# MK-312BT_V1_2.net
KiCad netlist of a schematic drawn in EAGLE
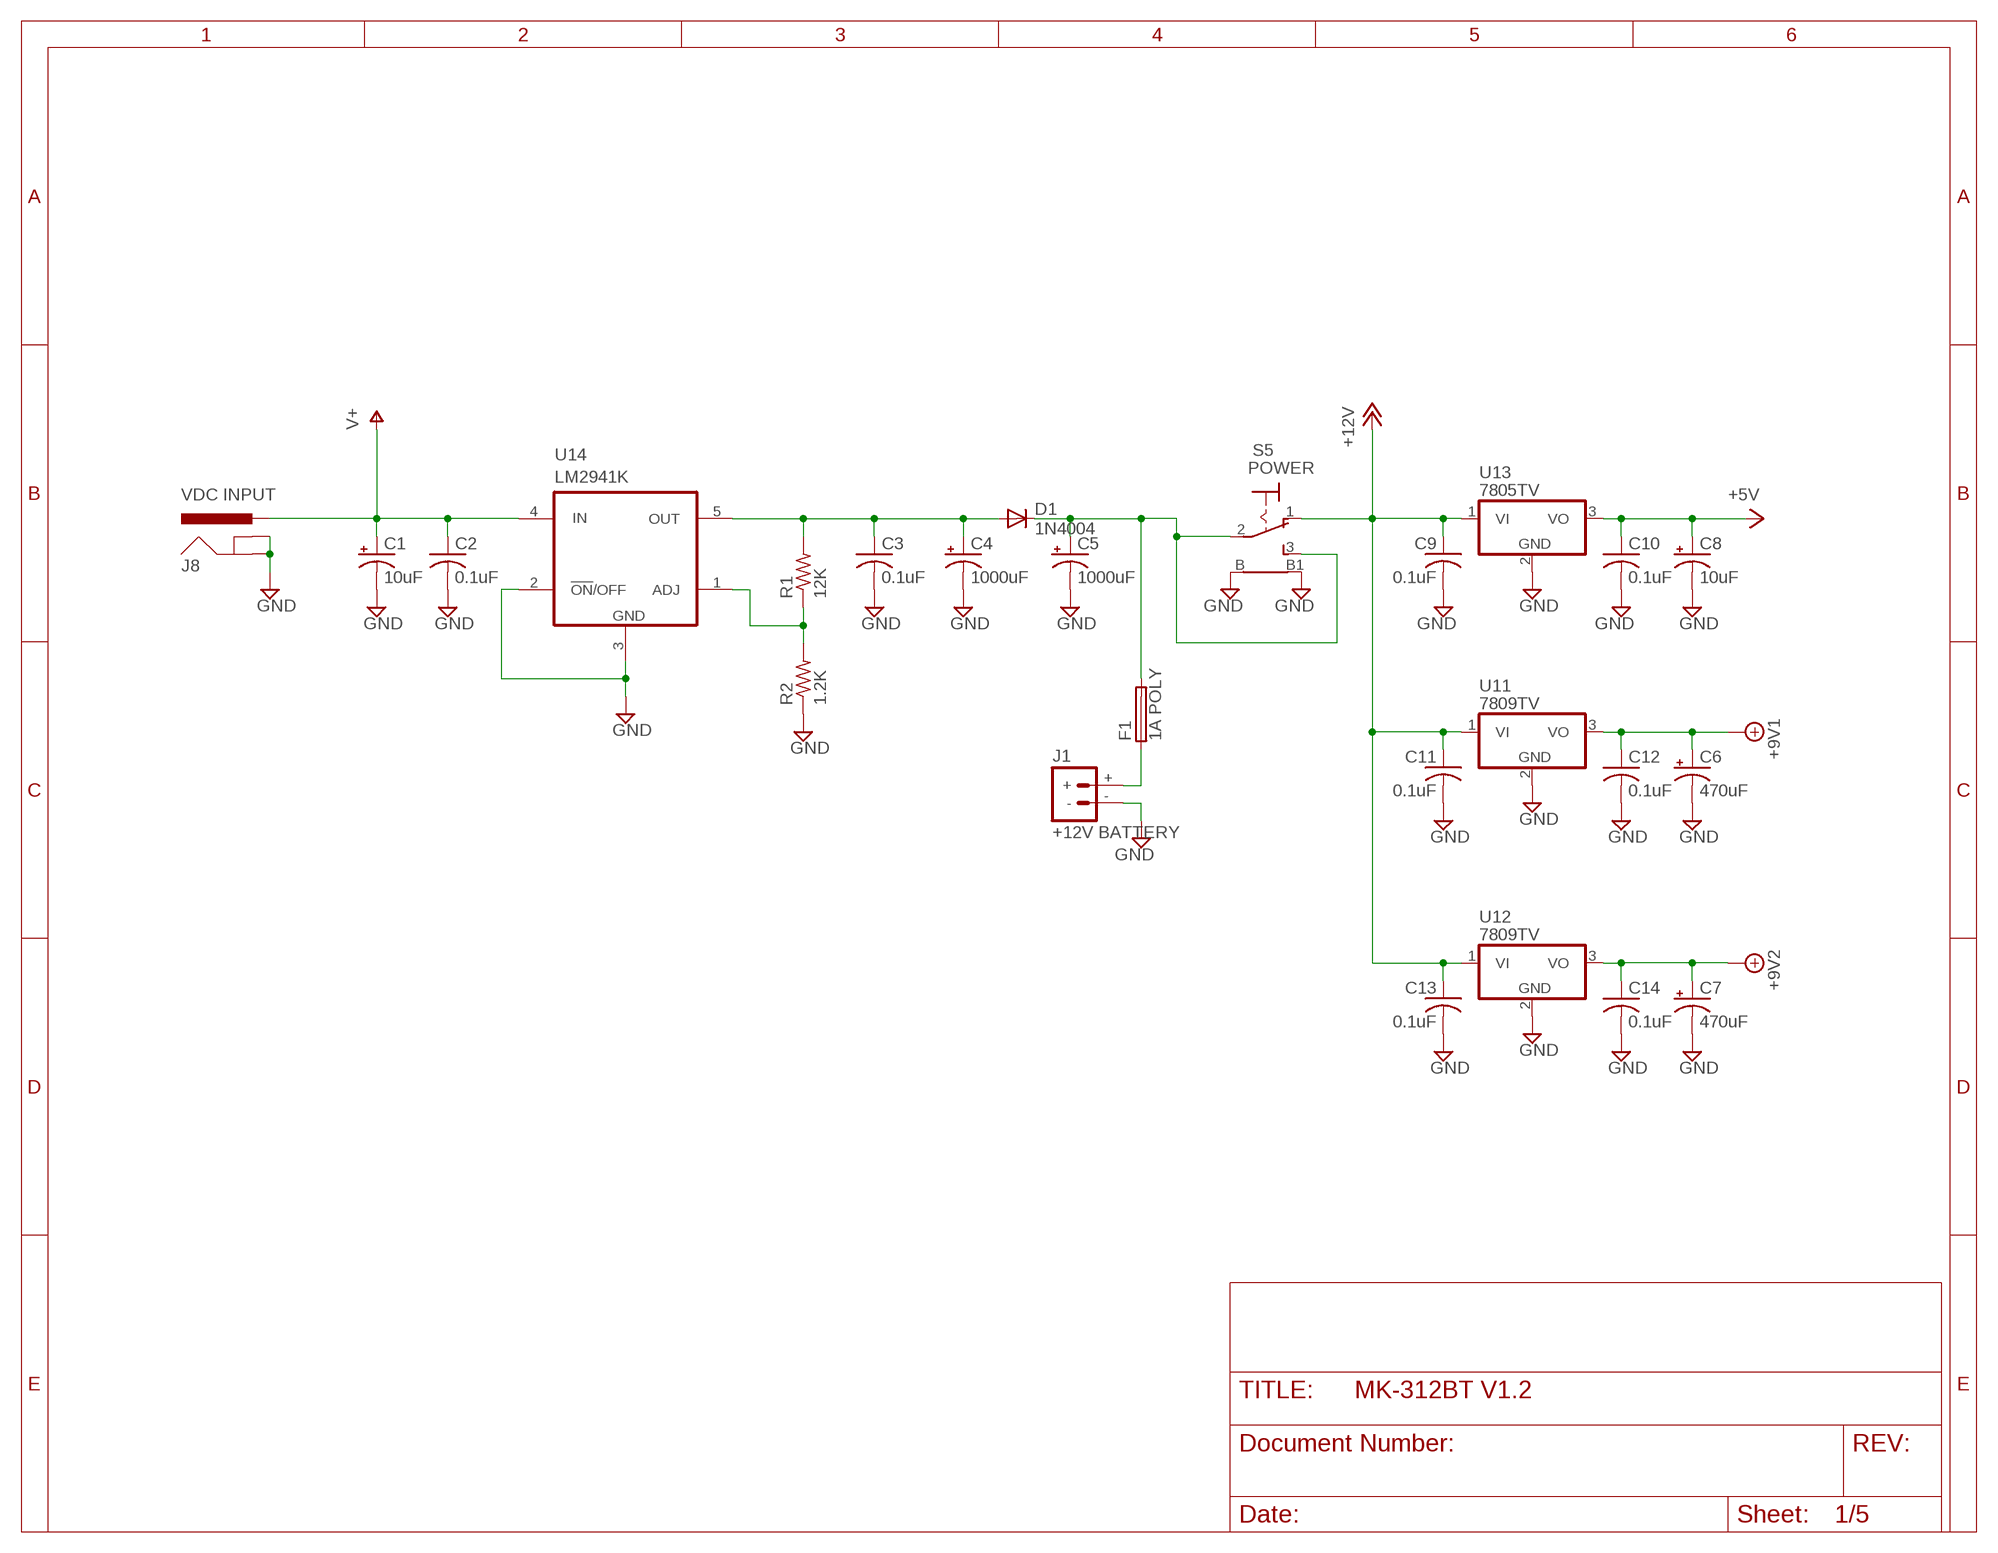
[diagram p0: schematic, sheet 1]
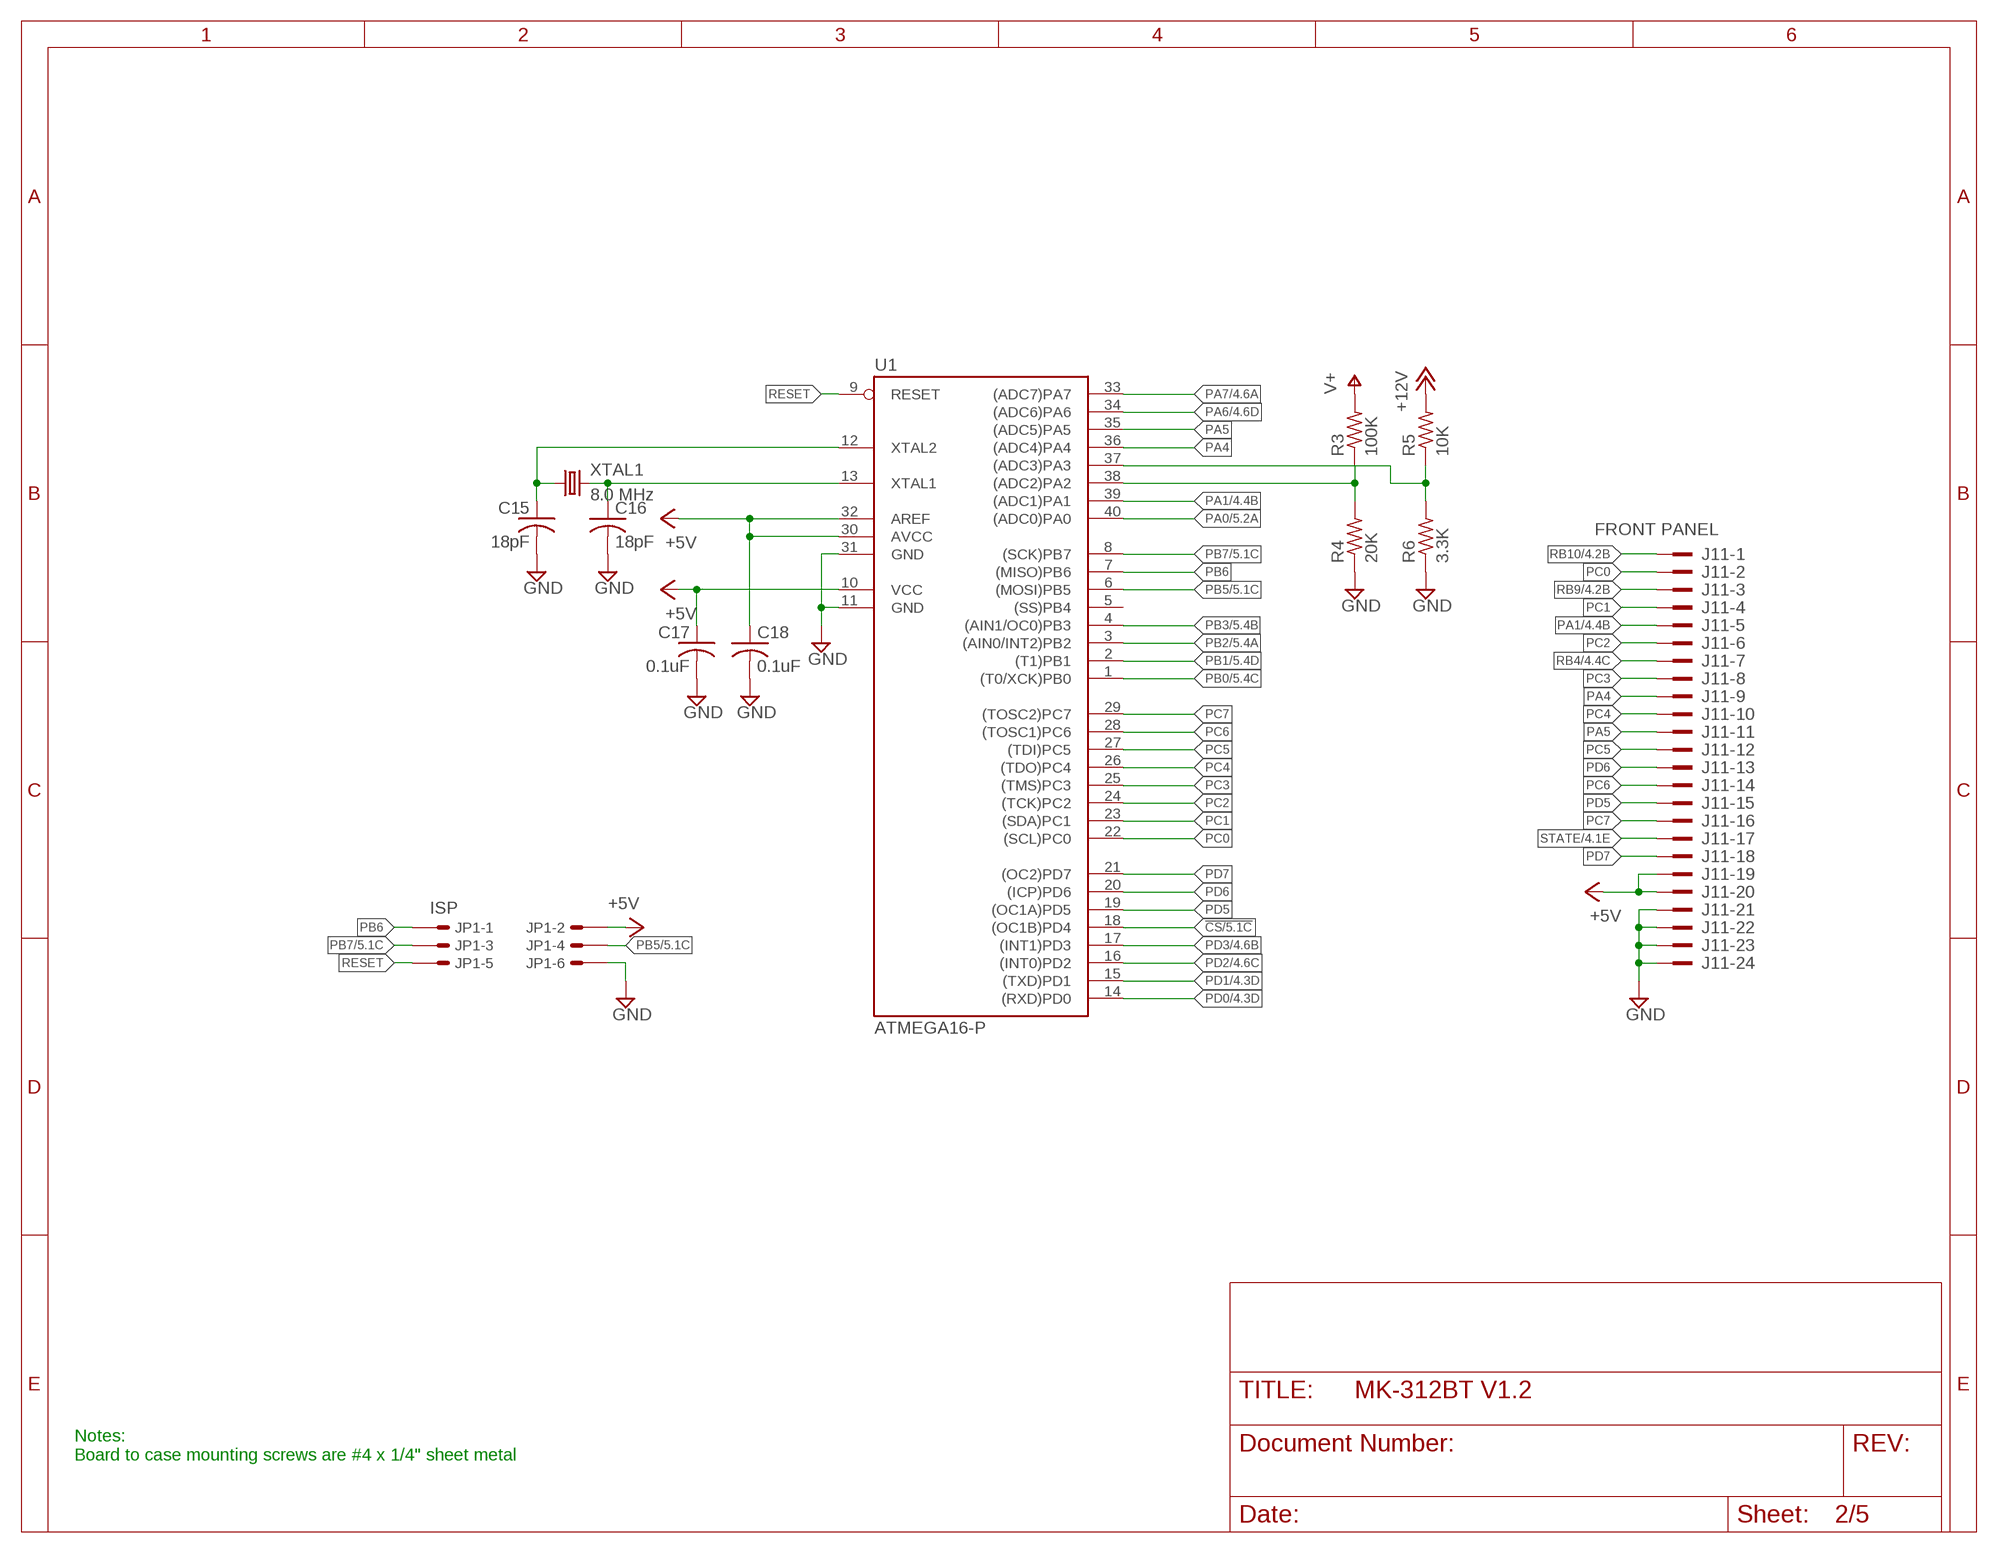
[diagram p1: schematic, sheet 2]
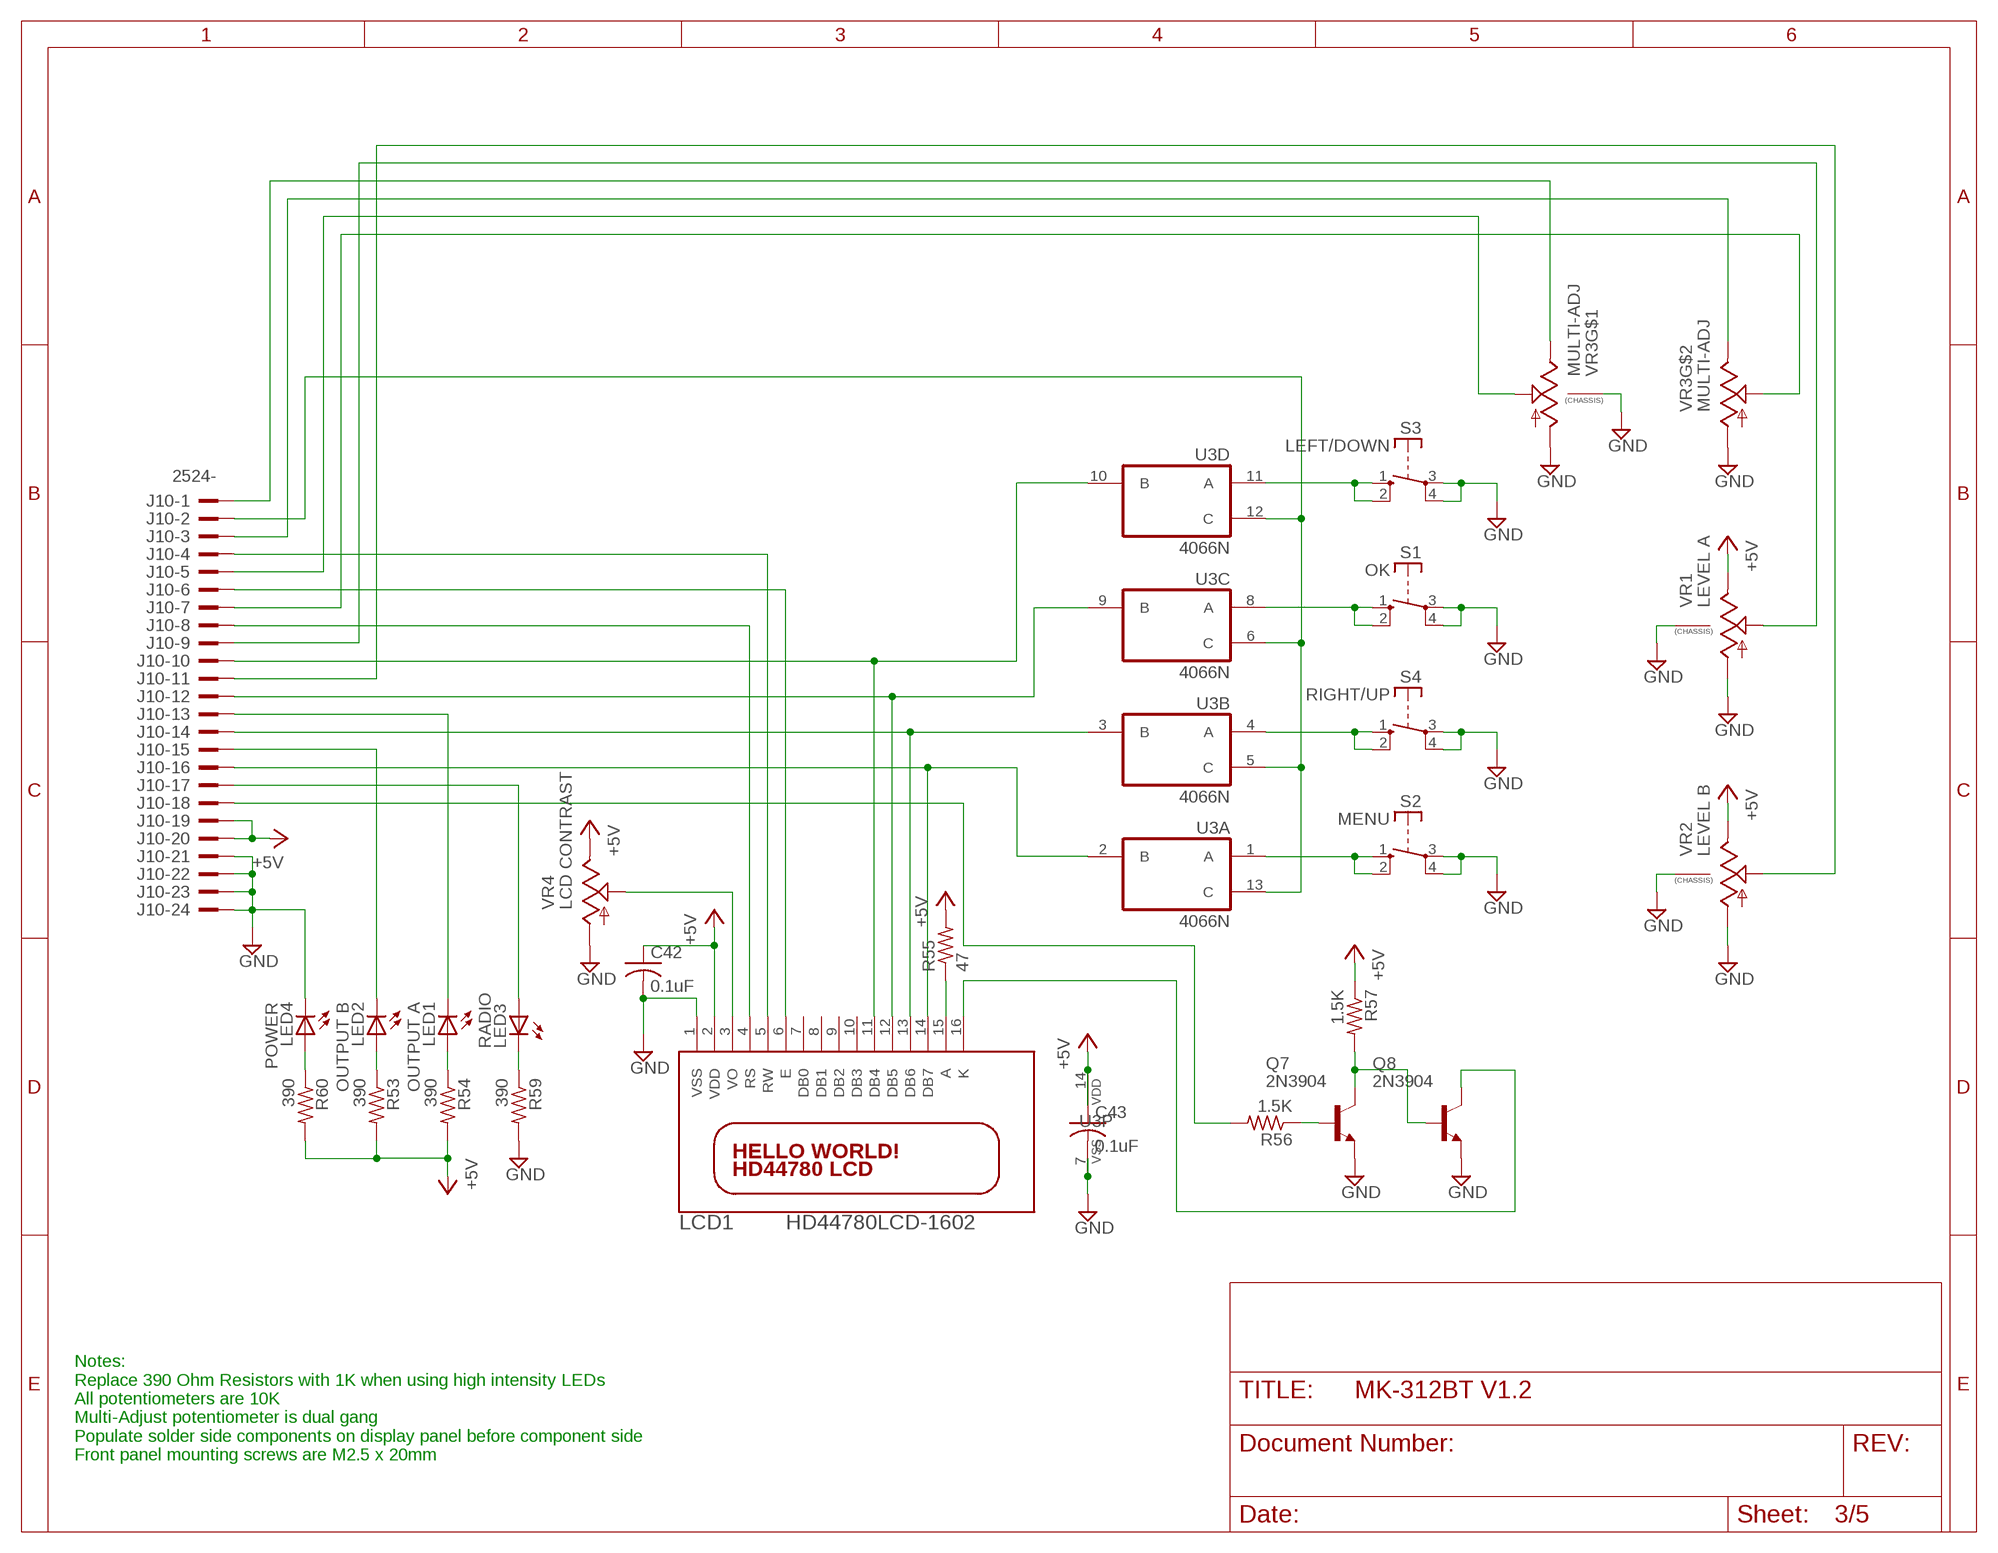
[diagram p2: schematic, sheet 3]
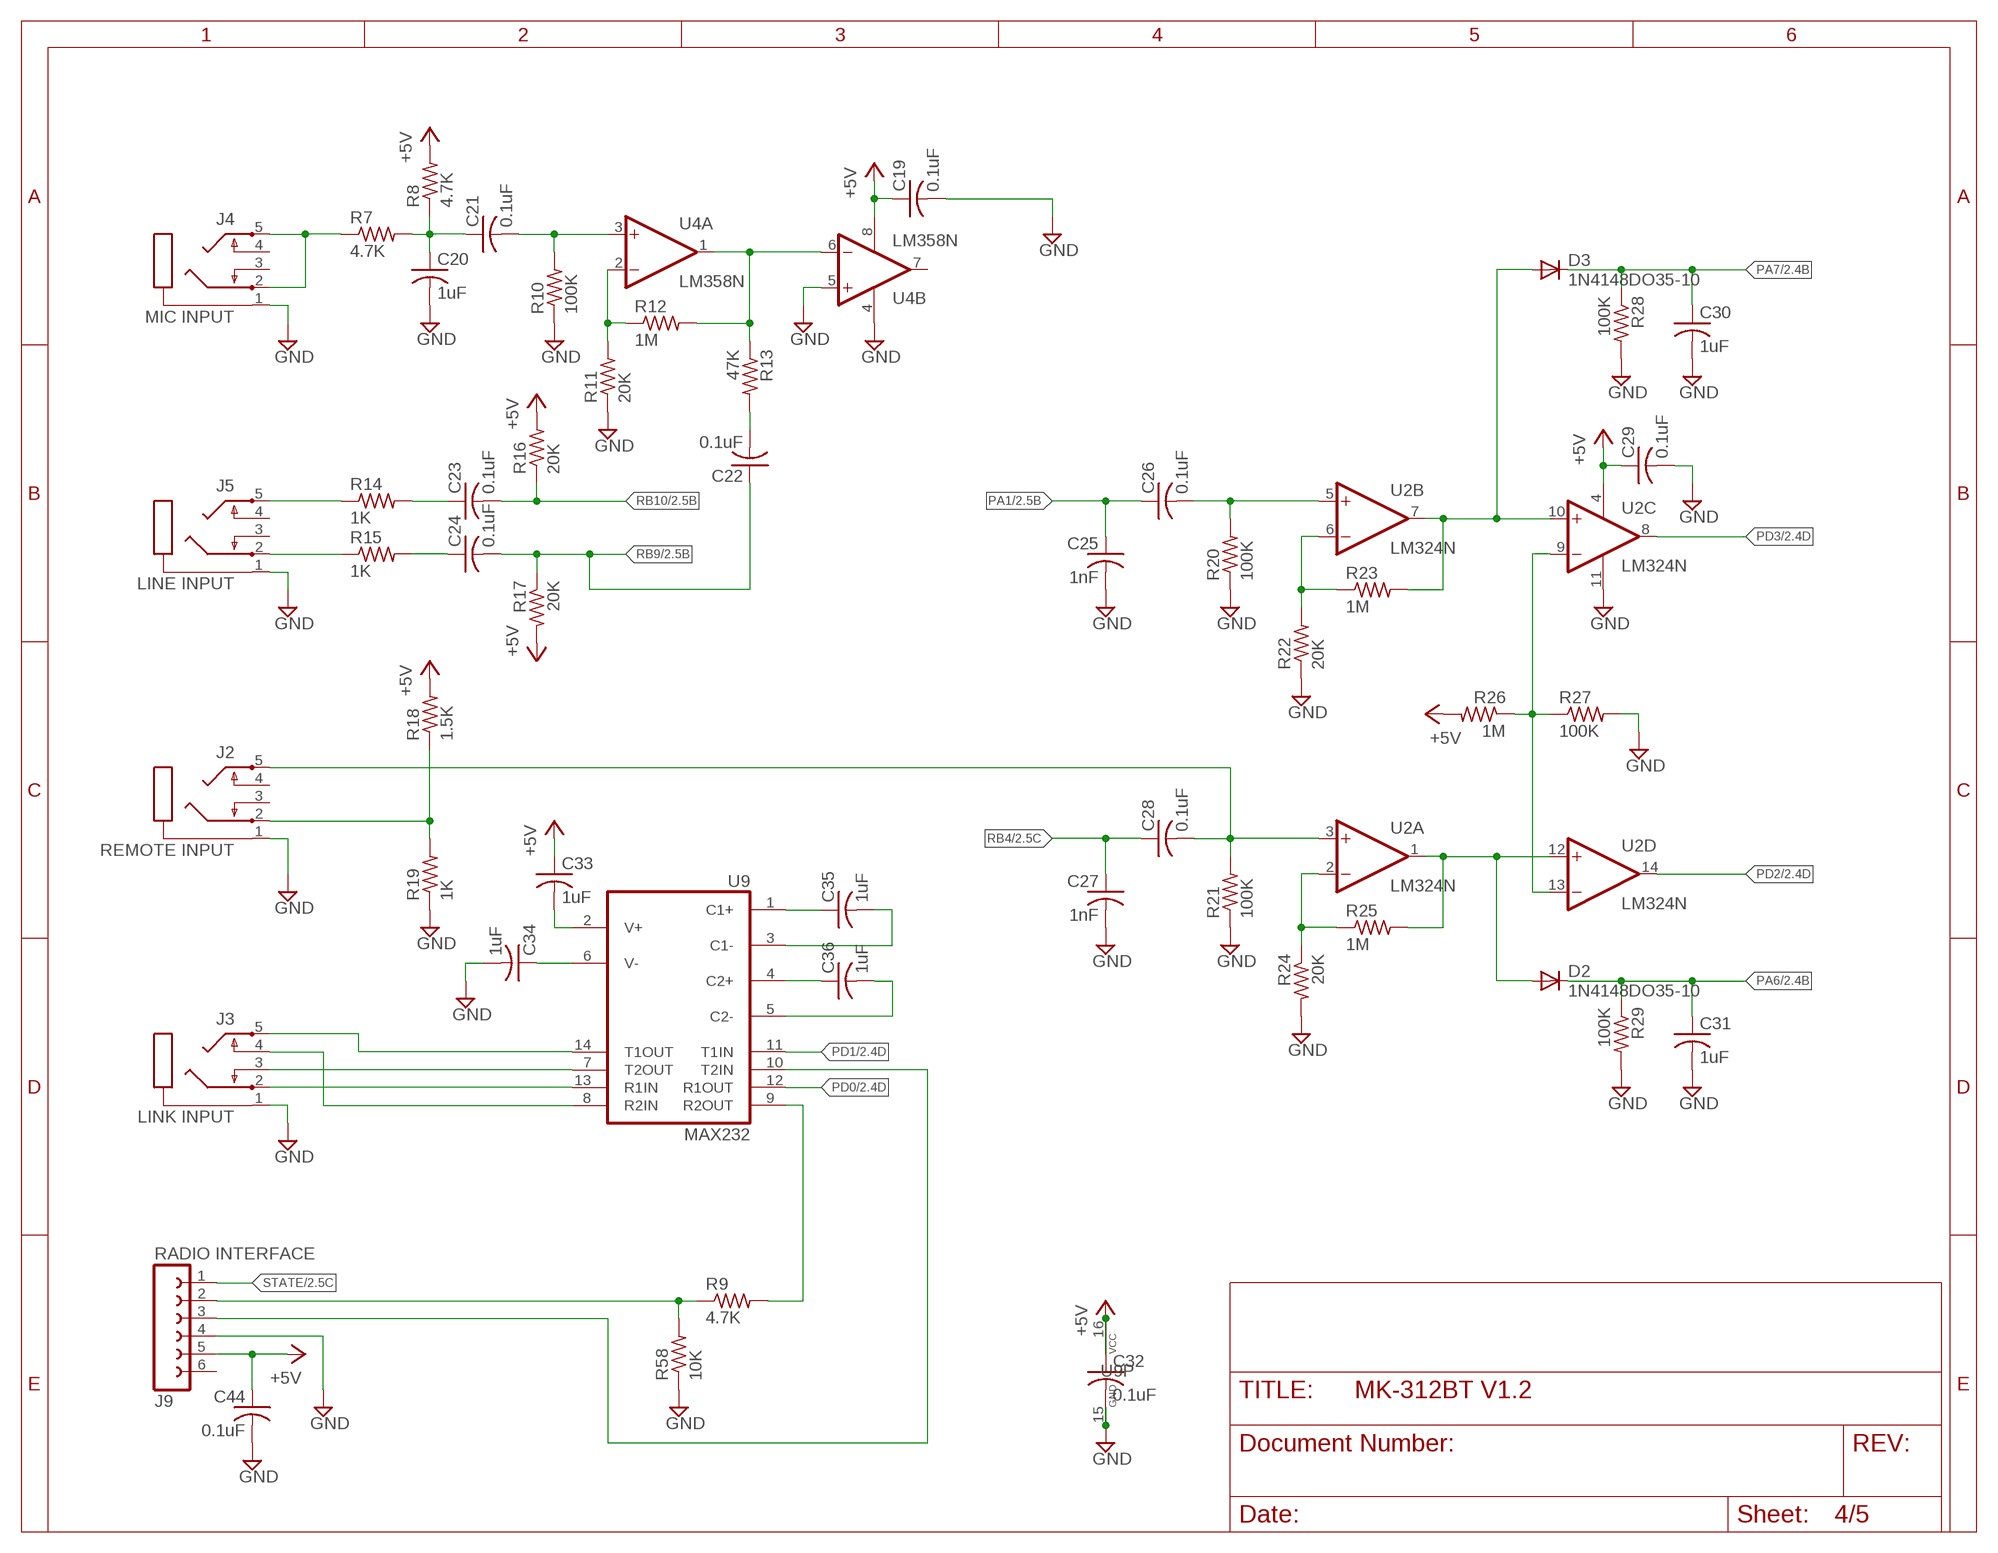
[diagram p3: schematic, sheet 4]
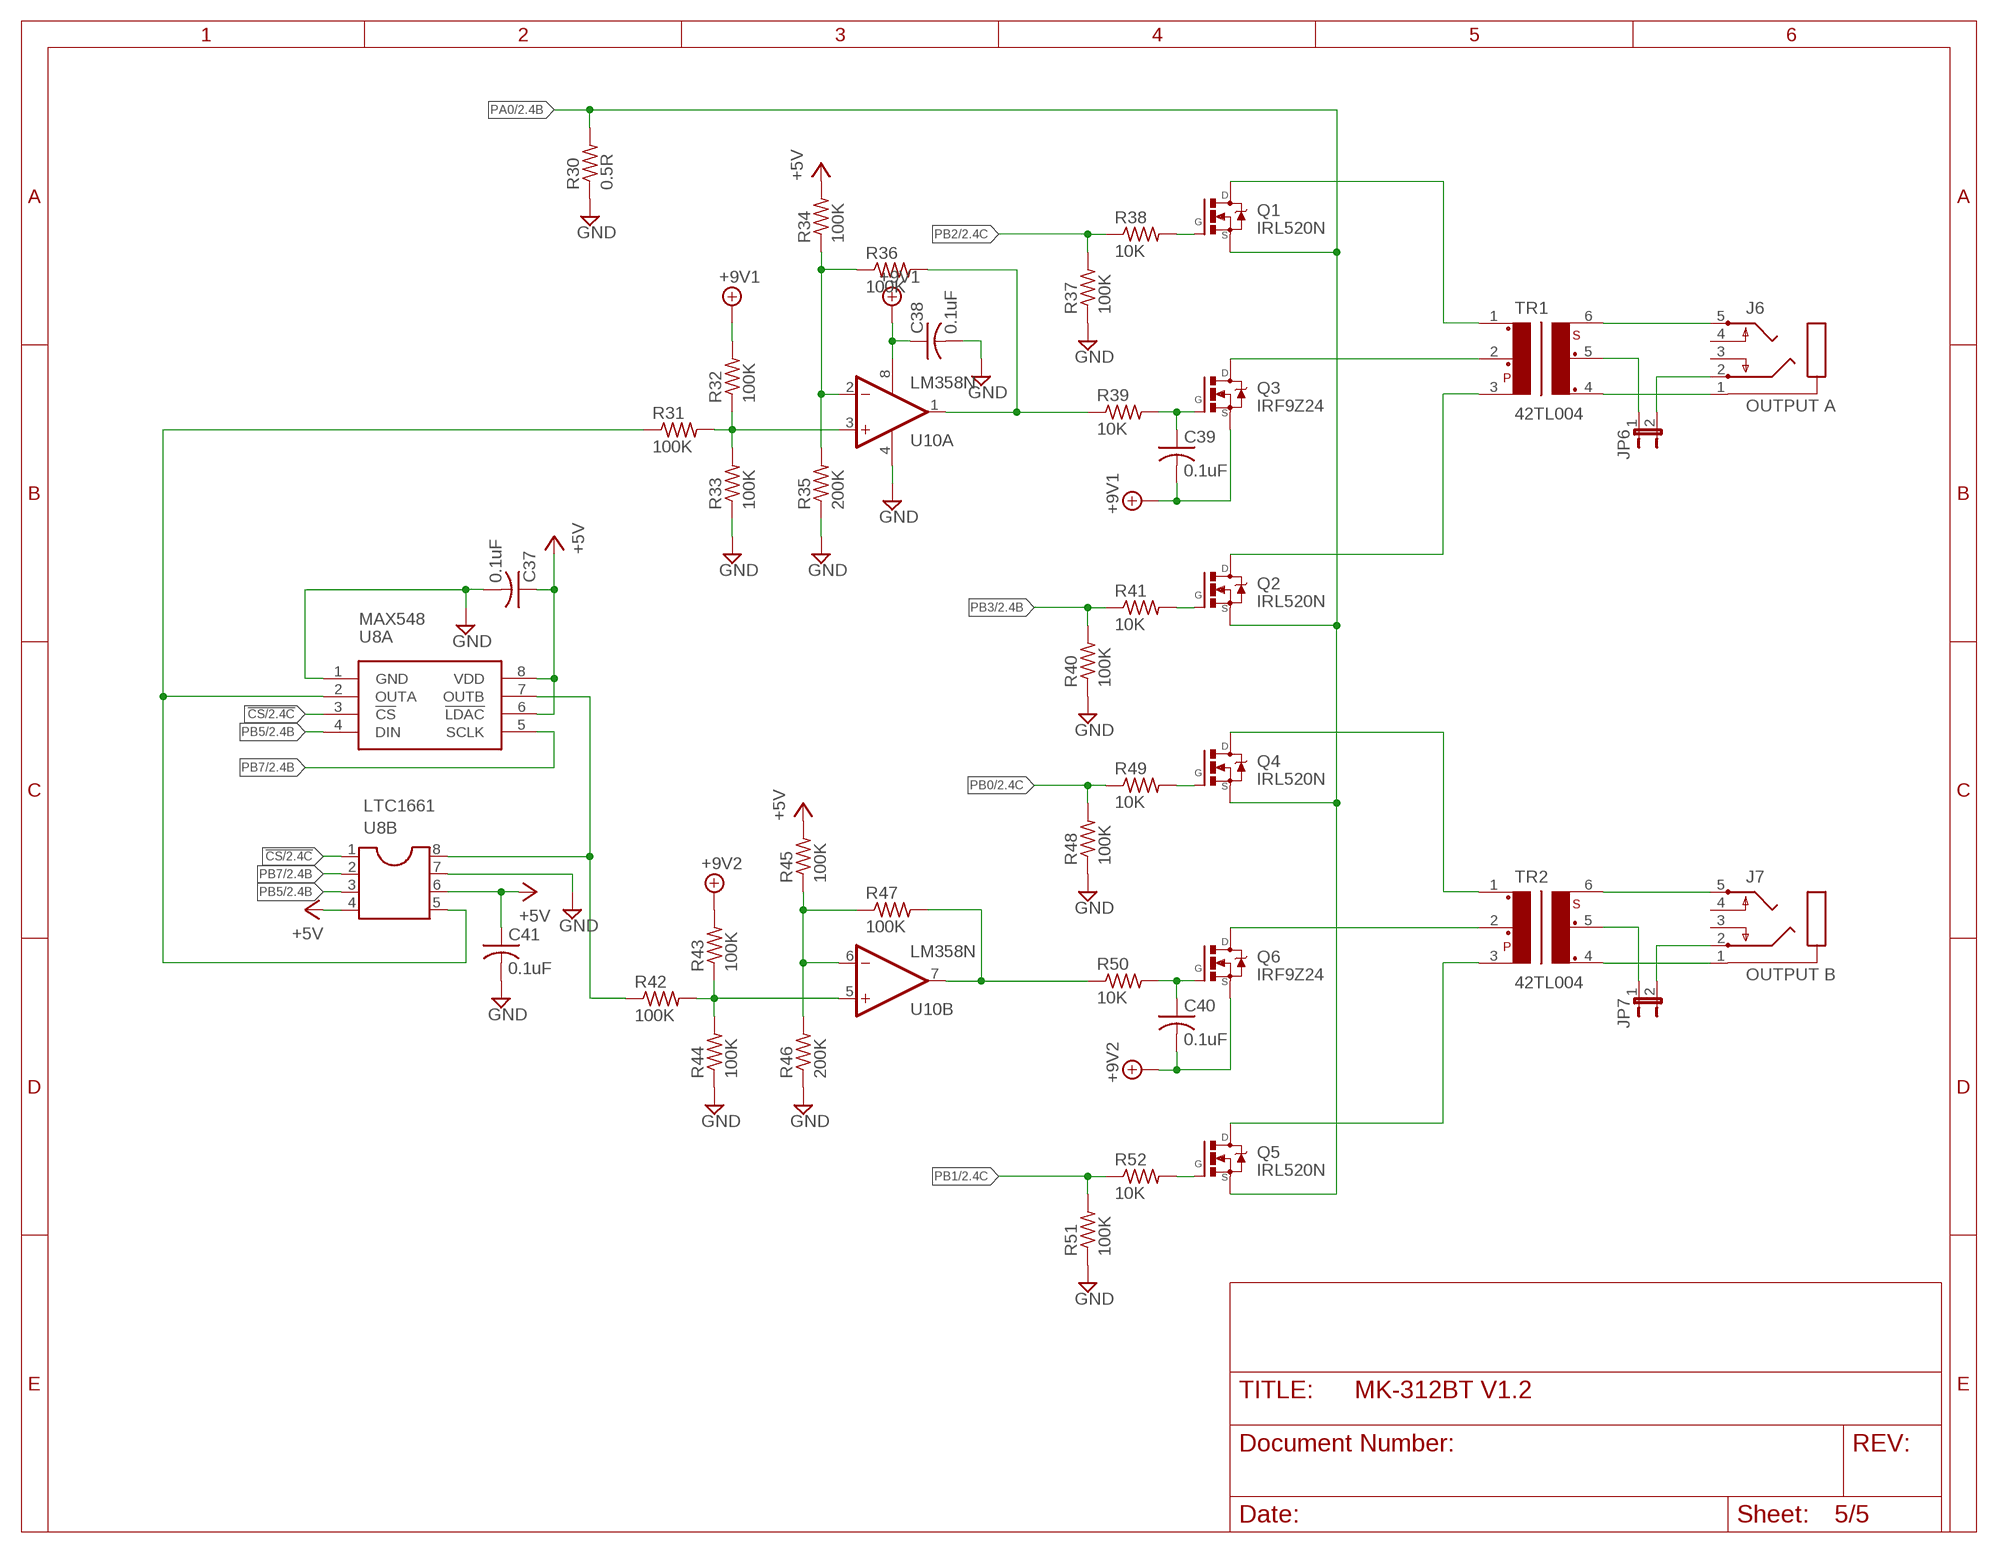
[diagram p4: schematic, sheet 5]

(export (version "E")
  (design (tool "Eeschema 10.0.6"))
  (components
    (comp (ref "C42")
      (value "0.1uF")
      (footprint "eagle-import:C025-024X044")
      (libsource (lib "eagle-import") (part "C-US025-024X044"))
    )
    (comp (ref "C43")
      (value "0.1uF")
      (footprint "eagle-import:C025-024X044")
      (libsource (lib "eagle-import") (part "C-US025-024X044"))
    )
    (comp (ref "J10")
      (value "2524-")
      (footprint "eagle-import:PAK100_2500-24")
      (libsource (lib "eagle-import") (part "2524-"))
    )
    (comp (ref "LCD1")
      (value "HD44780LCD-1602")
      (footprint "eagle-import:LCD1602")
      (libsource (lib "eagle-import") (part "HD44780LCD-1602"))
    )
    (comp (ref "LED1")
      (value "OUTPUT A")
      (footprint "eagle-import:LED5MM")
      (libsource (lib "eagle-import") (part "LED5MM"))
    )
    (comp (ref "LED2")
      (value "OUTPUT B")
      (footprint "eagle-import:LED5MM")
      (libsource (lib "eagle-import") (part "LED5MM"))
    )
    (comp (ref "LED3")
      (value "RADIO")
      (footprint "eagle-import:LED5MM")
      (libsource (lib "eagle-import") (part "LED5MM"))
    )
    (comp (ref "LED4")
      (value "POWER")
      (footprint "eagle-import:LED5MM")
      (libsource (lib "eagle-import") (part "LED5MM"))
    )
    (comp (ref "Q7")
      (value "2N3904")
      (footprint "eagle-import:TO92")
      (libsource (lib "eagle-import") (part "2N3904"))
    )
    (comp (ref "Q8")
      (value "2N3904")
      (footprint "eagle-import:TO92")
      (libsource (lib "eagle-import") (part "2N3904"))
    )
    (comp (ref "R53")
      (value "390")
      (footprint "eagle-import:0207_10")
      (libsource (lib "eagle-import") (part "R-US_0207/10"))
    )
    (comp (ref "R54")
      (value "390")
      (footprint "eagle-import:0207_10")
      (libsource (lib "eagle-import") (part "R-US_0207/10"))
    )
    (comp (ref "R55")
      (value "47")
      (footprint "eagle-import:0207_10")
      (libsource (lib "eagle-import") (part "R-US_0207/10"))
    )
    (comp (ref "R56")
      (value "1.5K")
      (footprint "eagle-import:0207_10")
      (libsource (lib "eagle-import") (part "R-US_0207/10"))
    )
    (comp (ref "R57")
      (value "1.5K")
      (footprint "eagle-import:0207_10")
      (libsource (lib "eagle-import") (part "R-US_0207/10"))
    )
    (comp (ref "R59")
      (value "390")
      (footprint "eagle-import:0207_10")
      (libsource (lib "eagle-import") (part "R-US_0207/10"))
    )
    (comp (ref "R60")
      (value "390")
      (footprint "eagle-import:0207_10")
      (libsource (lib "eagle-import") (part "R-US_0207/10"))
    )
    (comp (ref "S1")
      (value "OK")
      (footprint "eagle-import:DTE6K")
      (libsource (lib "eagle-import") (part "DTE6K"))
    )
    (comp (ref "S2")
      (value "MENU")
      (footprint "eagle-import:DTE6K")
      (libsource (lib "eagle-import") (part "DTE6K"))
    )
    (comp (ref "S3")
      (value "LEFT/DOWN")
      (footprint "eagle-import:DTE6K")
      (libsource (lib "eagle-import") (part "DTE6K"))
    )
    (comp (ref "S4")
      (value "RIGHT/UP")
      (footprint "eagle-import:DTE6K")
      (libsource (lib "eagle-import") (part "DTE6K"))
    )
    (comp (ref "U3")
      (value "4066N")
      (footprint "eagle-import:DIL14")
      (libsource (lib "eagle-import") (part "4066N"))
    )
    (comp (ref "VR1")
      (value "LEVEL A")
      (footprint "eagle-import:9MM_SNAP-IN_POT")
      (libsource (lib "eagle-import") (part "9MM_SNAP-IN_POT_CHASSIS"))
    )
    (comp (ref "VR2")
      (value "LEVEL B")
      (footprint "eagle-import:9MM_SNAP-IN_POT")
      (libsource (lib "eagle-import") (part "9MM_SNAP-IN_POT_CHASSIS"))
    )
    (comp (ref "VR3")
      (value "MULTI-ADJ")
      (footprint "eagle-import:DUAL_9MM_SNAP-IN_POT")
      (libsource (lib "eagle-import") (part "ALPHA-9MM-DUALPOT"))
    )
    (comp (ref "VR4")
      (value "LCD CONTRAST")
      (footprint "eagle-import:B25P")
      (libsource (lib "eagle-import") (part "TRIM_US-B25P"))
    )
    (comp (ref "C19")
      (value "0.1uF")
      (footprint "eagle-import:C025-024X044")
      (libsource (lib "eagle-import") (part "C-US025-024X044"))
    )
    (comp (ref "C20")
      (value "1uF")
      (footprint "eagle-import:C025-024X044")
      (libsource (lib "eagle-import") (part "C-US025-024X044"))
    )
    (comp (ref "C21")
      (value "0.1uF")
      (footprint "eagle-import:C025-024X044")
      (libsource (lib "eagle-import") (part "C-US025-024X044"))
    )
    (comp (ref "C22")
      (value "0.1uF")
      (footprint "eagle-import:C025-024X044")
      (libsource (lib "eagle-import") (part "C-US025-024X044"))
    )
    (comp (ref "C23")
      (value "0.1uF")
      (footprint "eagle-import:C025-024X044")
      (libsource (lib "eagle-import") (part "C-US025-024X044"))
    )
    (comp (ref "C24")
      (value "0.1uF")
      (footprint "eagle-import:C025-024X044")
      (libsource (lib "eagle-import") (part "C-US025-024X044"))
    )
    (comp (ref "C25")
      (value "1nF")
      (footprint "eagle-import:C025-024X044")
      (libsource (lib "eagle-import") (part "C-US025-024X044"))
    )
    (comp (ref "C26")
      (value "0.1uF")
      (footprint "eagle-import:C025-024X044")
      (libsource (lib "eagle-import") (part "C-US025-024X044"))
    )
    (comp (ref "C27")
      (value "1nF")
      (footprint "eagle-import:C025-024X044")
      (libsource (lib "eagle-import") (part "C-US025-024X044"))
    )
    (comp (ref "C28")
      (value "0.1uF")
      (footprint "eagle-import:C025-024X044")
      (libsource (lib "eagle-import") (part "C-US025-024X044"))
    )
    (comp (ref "C29")
      (value "0.1uF")
      (footprint "eagle-import:C025-024X044")
      (libsource (lib "eagle-import") (part "C-US025-024X044"))
    )
    (comp (ref "C30")
      (value "1uF")
      (footprint "eagle-import:C025-024X044")
      (libsource (lib "eagle-import") (part "C-US025-024X044"))
    )
    (comp (ref "C31")
      (value "1uF")
      (footprint "eagle-import:C025-024X044")
      (libsource (lib "eagle-import") (part "C-US025-024X044"))
    )
    (comp (ref "C32")
      (value "0.1uF")
      (footprint "eagle-import:C025-024X044")
      (libsource (lib "eagle-import") (part "C-US025-024X044"))
    )
    (comp (ref "C33")
      (value "1uF")
      (footprint "eagle-import:C025-024X044")
      (libsource (lib "eagle-import") (part "C-US025-024X044"))
    )
    (comp (ref "C34")
      (value "1uF")
      (footprint "eagle-import:C025-024X044")
      (libsource (lib "eagle-import") (part "C-US025-024X044"))
    )
    (comp (ref "C35")
      (value "1uF")
      (footprint "eagle-import:C025-024X044")
      (libsource (lib "eagle-import") (part "C-US025-024X044"))
    )
    (comp (ref "C36")
      (value "1uF")
      (footprint "eagle-import:C025-024X044")
      (libsource (lib "eagle-import") (part "C-US025-024X044"))
    )
    (comp (ref "C44")
      (value "0.1uF")
      (footprint "eagle-import:C025-024X044")
      (libsource (lib "eagle-import") (part "C-US025-024X044"))
    )
    (comp (ref "D2")
      (value "1N4148DO35-10")
      (footprint "eagle-import:DO35-10")
      (libsource (lib "eagle-import") (part "1N4148DO35-10"))
    )
    (comp (ref "D3")
      (value "1N4148DO35-10")
      (footprint "eagle-import:DO35-10")
      (libsource (lib "eagle-import") (part "1N4148DO35-10"))
    )
    (comp (ref "J2")
      (value "REMOTE INPUT")
      (footprint "eagle-import:STX3100")
      (libsource (lib "eagle-import") (part "STEREOJACK"))
    )
    (comp (ref "J3")
      (value "LINK INPUT")
      (footprint "eagle-import:STX3100")
      (libsource (lib "eagle-import") (part "STEREOJACK"))
    )
    (comp (ref "J4")
      (value "MIC INPUT")
      (footprint "eagle-import:STX3100")
      (libsource (lib "eagle-import") (part "STEREOJACK"))
    )
    (comp (ref "J5")
      (value "LINE INPUT")
      (footprint "eagle-import:STX3100")
      (libsource (lib "eagle-import") (part "STEREOJACK"))
    )
    (comp (ref "J9")
      (value "RADIO INTERFACE")
      (footprint "eagle-import:FE06")
      (libsource (lib "eagle-import") (part "FE06-1"))
    )
    (comp (ref "R7")
      (value "4.7K")
      (footprint "eagle-import:0207_10")
      (libsource (lib "eagle-import") (part "R-US_0207/10"))
    )
    (comp (ref "R8")
      (value "4.7K")
      (footprint "eagle-import:0207_10")
      (libsource (lib "eagle-import") (part "R-US_0207/10"))
    )
    (comp (ref "R9")
      (value "4.7K")
      (footprint "eagle-import:0207_10")
      (libsource (lib "eagle-import") (part "R-US_0207/10"))
    )
    (comp (ref "R10")
      (value "100K")
      (footprint "eagle-import:0207_10")
      (libsource (lib "eagle-import") (part "R-US_0207/10"))
    )
    (comp (ref "R11")
      (value "20K")
      (footprint "eagle-import:0207_10")
      (libsource (lib "eagle-import") (part "R-US_0207/10"))
    )
    (comp (ref "R12")
      (value "1M")
      (footprint "eagle-import:0207_10")
      (libsource (lib "eagle-import") (part "R-US_0207/10"))
    )
    (comp (ref "R13")
      (value "47K")
      (footprint "eagle-import:0207_10")
      (libsource (lib "eagle-import") (part "R-US_0207/10"))
    )
    (comp (ref "R14")
      (value "1K")
      (footprint "eagle-import:0207_10")
      (libsource (lib "eagle-import") (part "R-US_0207/10"))
    )
    (comp (ref "R15")
      (value "1K")
      (footprint "eagle-import:0207_10")
      (libsource (lib "eagle-import") (part "R-US_0207/10"))
    )
    (comp (ref "R16")
      (value "20K")
      (footprint "eagle-import:0207_10")
      (libsource (lib "eagle-import") (part "R-US_0207/10"))
    )
    (comp (ref "R17")
      (value "20K")
      (footprint "eagle-import:0207_10")
      (libsource (lib "eagle-import") (part "R-US_0207/10"))
    )
    (comp (ref "R18")
      (value "1.5K")
      (footprint "eagle-import:0207_10")
      (libsource (lib "eagle-import") (part "R-US_0207/10"))
    )
    (comp (ref "R19")
      (value "1K")
      (footprint "eagle-import:0207_10")
      (libsource (lib "eagle-import") (part "R-US_0207/10"))
    )
    (comp (ref "R20")
      (value "100K")
      (footprint "eagle-import:0207_10")
      (libsource (lib "eagle-import") (part "R-US_0207/10"))
    )
    (comp (ref "R21")
      (value "100K")
      (footprint "eagle-import:0207_10")
      (libsource (lib "eagle-import") (part "R-US_0207/10"))
    )
    (comp (ref "R22")
      (value "20K")
      (footprint "eagle-import:0207_10")
      (libsource (lib "eagle-import") (part "R-US_0207/10"))
    )
    (comp (ref "R23")
      (value "1M")
      (footprint "eagle-import:0207_10")
      (libsource (lib "eagle-import") (part "R-US_0207/10"))
    )
    (comp (ref "R24")
      (value "20K")
      (footprint "eagle-import:0207_10")
      (libsource (lib "eagle-import") (part "R-US_0207/10"))
    )
    (comp (ref "R25")
      (value "1M")
      (footprint "eagle-import:0207_10")
      (libsource (lib "eagle-import") (part "R-US_0207/10"))
    )
    (comp (ref "R26")
      (value "1M")
      (footprint "eagle-import:0207_10")
      (libsource (lib "eagle-import") (part "R-US_0207/10"))
    )
    (comp (ref "R27")
      (value "100K")
      (footprint "eagle-import:0207_10")
      (libsource (lib "eagle-import") (part "R-US_0207/10"))
    )
    (comp (ref "R28")
      (value "100K")
      (footprint "eagle-import:0207_10")
      (libsource (lib "eagle-import") (part "R-US_0207/10"))
    )
    (comp (ref "R29")
      (value "100K")
      (footprint "eagle-import:0207_10")
      (libsource (lib "eagle-import") (part "R-US_0207/10"))
    )
    (comp (ref "R58")
      (value "10K")
      (footprint "eagle-import:0207_10")
      (libsource (lib "eagle-import") (part "R-US_0207/10"))
    )
    (comp (ref "U2")
      (value "LM324N")
      (footprint "eagle-import:DIL14")
      (libsource (lib "eagle-import") (part "LM324N"))
    )
    (comp (ref "U4")
      (value "LM358N")
      (footprint "eagle-import:DIL08")
      (libsource (lib "eagle-import") (part "LM358N"))
    )
    (comp (ref "U9")
      (value "MAX232")
      (footprint "eagle-import:DIL16")
      (fields (field (name "MF") "MAXIM") (field (name "MPN") "MAX232ACPE+"))
      (libsource (lib "eagle-import") (part "MAX232"))
    )
    (comp (ref "C15")
      (value "18pF")
      (footprint "eagle-import:C025-024X044")
      (libsource (lib "eagle-import") (part "C-US025-024X044"))
    )
    (comp (ref "C16")
      (value "18pF")
      (footprint "eagle-import:C025-024X044")
      (libsource (lib "eagle-import") (part "C-US025-024X044"))
    )
    (comp (ref "C17")
      (value "0.1uF")
      (footprint "eagle-import:C025-024X044")
      (libsource (lib "eagle-import") (part "C-US025-024X044"))
    )
    (comp (ref "C18")
      (value "0.1uF")
      (footprint "eagle-import:C025-024X044")
      (libsource (lib "eagle-import") (part "C-US025-024X044"))
    )
    (comp (ref "J11")
      (value "FRONT PANEL")
      (footprint "eagle-import:PAK100_2500-24")
      (libsource (lib "eagle-import") (part "2524-"))
    )
    (comp (ref "JP1")
      (value "ISP")
      (footprint "eagle-import:057-006-1")
      (libsource (lib "eagle-import") (part "057-006-1"))
    )
    (comp (ref "R3")
      (value "100K")
      (footprint "eagle-import:0207_10")
      (libsource (lib "eagle-import") (part "R-US_0207/10"))
    )
    (comp (ref "R4")
      (value "20K")
      (footprint "eagle-import:0207_10")
      (libsource (lib "eagle-import") (part "R-US_0207/10"))
    )
    (comp (ref "R5")
      (value "10K")
      (footprint "eagle-import:0207_10")
      (libsource (lib "eagle-import") (part "R-US_0207/10"))
    )
    (comp (ref "R6")
      (value "3.3K")
      (footprint "eagle-import:0207_10")
      (libsource (lib "eagle-import") (part "R-US_0207/10"))
    )
    (comp (ref "U1")
      (value "ATMEGA16-P")
      (footprint "eagle-import:DIL40")
      (fields (field (name "MPN") "ATMEGA16-16PU"))
      (libsource (lib "eagle-import") (part "MEGA16-P"))
    )
    (comp (ref "XTAL1")
      (value "8.0 MHz")
      (footprint "eagle-import:HC49_S")
      (libsource (lib "eagle-import") (part "CRYSTALHC49S"))
    )
    (comp (ref "C37")
      (value "0.1uF")
      (footprint "eagle-import:C025-024X044")
      (libsource (lib "eagle-import") (part "C-US025-024X044"))
    )
    (comp (ref "C38")
      (value "0.1uF")
      (footprint "eagle-import:C025-024X044")
      (libsource (lib "eagle-import") (part "C-US025-024X044"))
    )
    (comp (ref "C39")
      (value "0.1uF")
      (footprint "eagle-import:C025-024X044")
      (libsource (lib "eagle-import") (part "C-US025-024X044"))
    )
    (comp (ref "C40")
      (value "0.1uF")
      (footprint "eagle-import:C025-024X044")
      (libsource (lib "eagle-import") (part "C-US025-024X044"))
    )
    (comp (ref "C41")
      (value "0.1uF")
      (footprint "eagle-import:C025-024X044")
      (libsource (lib "eagle-import") (part "C-US025-024X044"))
    )
    (comp (ref "J6")
      (value "OUTPUT A")
      (footprint "eagle-import:STX3100")
      (libsource (lib "eagle-import") (part "STEREOJACK"))
    )
    (comp (ref "J7")
      (value "OUTPUT B")
      (footprint "eagle-import:STX3100")
      (libsource (lib "eagle-import") (part "STEREOJACK"))
    )
    (comp (ref "JP6")
      (value "JP1E")
      (footprint "eagle-import:JP1")
      (libsource (lib "eagle-import") (part "JP1E"))
    )
    (comp (ref "JP7")
      (value "JP1E")
      (footprint "eagle-import:JP1")
      (libsource (lib "eagle-import") (part "JP1E"))
    )
    (comp (ref "Q1")
      (value "IRL520N")
      (footprint "eagle-import:TO220V")
      (libsource (lib "eagle-import") (part "IRL530N-V"))
    )
    (comp (ref "Q2")
      (value "IRL520N")
      (footprint "eagle-import:TO220V")
      (libsource (lib "eagle-import") (part "IRL530N-V"))
    )
    (comp (ref "Q3")
      (value "IRF9Z24")
      (footprint "eagle-import:TO220V")
      (libsource (lib "eagle-import") (part "IRL530N-V"))
    )
    (comp (ref "Q4")
      (value "IRL520N")
      (footprint "eagle-import:TO220V")
      (libsource (lib "eagle-import") (part "IRL530N-V"))
    )
    (comp (ref "Q5")
      (value "IRL520N")
      (footprint "eagle-import:TO220V")
      (libsource (lib "eagle-import") (part "IRL530N-V"))
    )
    (comp (ref "Q6")
      (value "IRF9Z24")
      (footprint "eagle-import:TO220V")
      (libsource (lib "eagle-import") (part "IRL530N-V"))
    )
    (comp (ref "R30")
      (value "0.5R")
      (footprint "eagle-import:0309_12")
      (libsource (lib "eagle-import") (part "R-US_0309/12"))
    )
    (comp (ref "R31")
      (value "100K")
      (footprint "eagle-import:0207_10")
      (libsource (lib "eagle-import") (part "R-US_0207/10"))
    )
    (comp (ref "R32")
      (value "100K")
      (footprint "eagle-import:0207_10")
      (libsource (lib "eagle-import") (part "R-US_0207/10"))
    )
    (comp (ref "R33")
      (value "100K")
      (footprint "eagle-import:0207_10")
      (libsource (lib "eagle-import") (part "R-US_0207/10"))
    )
    (comp (ref "R34")
      (value "100K")
      (footprint "eagle-import:0207_10")
      (libsource (lib "eagle-import") (part "R-US_0207/10"))
    )
    (comp (ref "R35")
      (value "200K")
      (footprint "eagle-import:0207_10")
      (libsource (lib "eagle-import") (part "R-US_0207/10"))
    )
    (comp (ref "R36")
      (value "100K")
      (footprint "eagle-import:0207_10")
      (libsource (lib "eagle-import") (part "R-US_0207/10"))
    )
    (comp (ref "R37")
      (value "100K")
      (footprint "eagle-import:0207_10")
      (libsource (lib "eagle-import") (part "R-US_0207/10"))
    )
    (comp (ref "R38")
      (value "10K")
      (footprint "eagle-import:0207_10")
      (libsource (lib "eagle-import") (part "R-US_0207/10"))
    )
    (comp (ref "R39")
      (value "10K")
      (footprint "eagle-import:0207_10")
      (libsource (lib "eagle-import") (part "R-US_0207/10"))
    )
    (comp (ref "R40")
      (value "100K")
      (footprint "eagle-import:0207_10")
      (libsource (lib "eagle-import") (part "R-US_0207/10"))
    )
    (comp (ref "R41")
      (value "10K")
      (footprint "eagle-import:0207_10")
      (libsource (lib "eagle-import") (part "R-US_0207/10"))
    )
    (comp (ref "R42")
      (value "100K")
      (footprint "eagle-import:0207_10")
      (libsource (lib "eagle-import") (part "R-US_0207/10"))
    )
    (comp (ref "R43")
      (value "100K")
      (footprint "eagle-import:0207_10")
      (libsource (lib "eagle-import") (part "R-US_0207/10"))
    )
    (comp (ref "R44")
      (value "100K")
      (footprint "eagle-import:0207_10")
      (libsource (lib "eagle-import") (part "R-US_0207/10"))
    )
    (comp (ref "R45")
      (value "100K")
      (footprint "eagle-import:0207_10")
      (libsource (lib "eagle-import") (part "R-US_0207/10"))
    )
    (comp (ref "R46")
      (value "200K")
      (footprint "eagle-import:0207_10")
      (libsource (lib "eagle-import") (part "R-US_0207/10"))
    )
    (comp (ref "R47")
      (value "100K")
      (footprint "eagle-import:0207_10")
      (libsource (lib "eagle-import") (part "R-US_0207/10"))
    )
    (comp (ref "R48")
      (value "100K")
      (footprint "eagle-import:0207_10")
      (libsource (lib "eagle-import") (part "R-US_0207/10"))
    )
    (comp (ref "R49")
      (value "10K")
      (footprint "eagle-import:0207_10")
      (libsource (lib "eagle-import") (part "R-US_0207/10"))
    )
    (comp (ref "R50")
      (value "10K")
      (footprint "eagle-import:0207_10")
      (libsource (lib "eagle-import") (part "R-US_0207/10"))
    )
    (comp (ref "R51")
      (value "100K")
      (footprint "eagle-import:0207_10")
      (libsource (lib "eagle-import") (part "R-US_0207/10"))
    )
    (comp (ref "R52")
      (value "10K")
      (footprint "eagle-import:0207_10")
      (libsource (lib "eagle-import") (part "R-US_0207/10"))
    )
    (comp (ref "TR1")
      (value "42TL004")
      (footprint "eagle-import:42TL")
      (libsource (lib "eagle-import") (part "42T?L023"))
    )
    (comp (ref "TR2")
      (value "42TL004")
      (footprint "eagle-import:42TL")
      (libsource (lib "eagle-import") (part "42T?L023"))
    )
    (comp (ref "U8A")
      (value "MAX548")
      (footprint "eagle-import:DIL08")
      (libsource (lib "eagle-import") (part "MAX548"))
    )
    (comp (ref "U8B")
      (value "LTC1661")
      (footprint "eagle-import:SOCKET-08")
      (libsource (lib "eagle-import") (part "DIL8S"))
    )
    (comp (ref "U10")
      (value "LM358N")
      (footprint "eagle-import:DIL08")
      (libsource (lib "eagle-import") (part "LM358N"))
    )
    (comp (ref "C1")
      (value "10uF")
      (footprint "eagle-import:E2,5-7")
      (libsource (lib "eagle-import") (part "CPOL-USE2.5-7"))
    )
    (comp (ref "C2")
      (value "0.1uF")
      (footprint "eagle-import:C025-024X044")
      (libsource (lib "eagle-import") (part "C-US025-024X044"))
    )
    (comp (ref "C3")
      (value "0.1uF")
      (footprint "eagle-import:C025-024X044")
      (libsource (lib "eagle-import") (part "C-US025-024X044"))
    )
    (comp (ref "C4")
      (value "1000uF")
      (footprint "eagle-import:E5-10,5")
      (libsource (lib "eagle-import") (part "CPOL-USE5-10.5"))
    )
    (comp (ref "C5")
      (value "1000uF")
      (footprint "eagle-import:E5-10,5")
      (libsource (lib "eagle-import") (part "CPOL-USE5-10.5"))
    )
    (comp (ref "C6")
      (value "470uF")
      (footprint "eagle-import:E3,5-8")
      (libsource (lib "eagle-import") (part "CPOL-USE3.5-8"))
    )
    (comp (ref "C7")
      (value "470uF")
      (footprint "eagle-import:E3,5-8")
      (libsource (lib "eagle-import") (part "CPOL-USE3.5-8"))
    )
    (comp (ref "C8")
      (value "10uF")
      (footprint "eagle-import:E2,5-7")
      (libsource (lib "eagle-import") (part "CPOL-USE2.5-7"))
    )
    (comp (ref "C9")
      (value "0.1uF")
      (footprint "eagle-import:C025-024X044")
      (libsource (lib "eagle-import") (part "C-US025-024X044"))
    )
    (comp (ref "C10")
      (value "0.1uF")
      (footprint "eagle-import:C025-024X044")
      (libsource (lib "eagle-import") (part "C-US025-024X044"))
    )
    (comp (ref "C11")
      (value "0.1uF")
      (footprint "eagle-import:C025-024X044")
      (libsource (lib "eagle-import") (part "C-US025-024X044"))
    )
    (comp (ref "C12")
      (value "0.1uF")
      (footprint "eagle-import:C025-024X044")
      (libsource (lib "eagle-import") (part "C-US025-024X044"))
    )
    (comp (ref "C13")
      (value "0.1uF")
      (footprint "eagle-import:C025-024X044")
      (libsource (lib "eagle-import") (part "C-US025-024X044"))
    )
    (comp (ref "C14")
      (value "0.1uF")
      (footprint "eagle-import:C025-024X044")
      (libsource (lib "eagle-import") (part "C-US025-024X044"))
    )
    (comp (ref "D1")
      (value "1N4004")
      (footprint "eagle-import:DO41-10")
      (libsource (lib "eagle-import") (part "1N4004"))
    )
    (comp (ref "F1")
      (value "1A POLY")
      (footprint "eagle-import:LITTLEFUSE")
      (libsource (lib "eagle-import") (part "LITTLEFUSE"))
    )
    (comp (ref "J1")
      (value "+12V BATTERY")
      (footprint "eagle-import:DEANS")
      (libsource (lib "eagle-import") (part "BATTERY_CONNDEANS"))
    )
    (comp (ref "J8")
      (value "VDC INPUT")
      (footprint "eagle-import:POWER_JACK_SLOT")
      (libsource (lib "eagle-import") (part "POWER_JACKSLT"))
    )
    (comp (ref "R1")
      (value "12K")
      (footprint "eagle-import:0207_10")
      (libsource (lib "eagle-import") (part "R-US_0207/10"))
    )
    (comp (ref "R2")
      (value "1.2K")
      (footprint "eagle-import:0207_10")
      (libsource (lib "eagle-import") (part "R-US_0207/10"))
    )
    (comp (ref "S5")
      (value "POWER")
      (footprint "eagle-import:LPV-1")
      (libsource (lib "eagle-import") (part "LPV-1"))
    )
    (comp (ref "U11")
      (value "7809TV")
      (footprint "eagle-import:TO220V")
      (libsource (lib "eagle-import") (part "78TV05"))
    )
    (comp (ref "U12")
      (value "7809TV")
      (footprint "eagle-import:TO220V")
      (libsource (lib "eagle-import") (part "78TV05"))
    )
    (comp (ref "U13")
      (value "7805TV")
      (footprint "eagle-import:TO220V")
      (libsource (lib "eagle-import") (part "78TV05"))
    )
    (comp (ref "U14")
      (value "LM2941K")
      (footprint "eagle-import:TO220-5KC")
      (libsource (lib "eagle-import") (part "LM2941K"))
    )
  )
  (nets
    (net (code "1") (name "+5V") (class "Default")
      (node (ref "C10") (pin "1") (pinfunction "1_1") (pintype "passive"))
      (node (ref "C17") (pin "1") (pinfunction "1_1") (pintype "passive"))
      (node (ref "C18") (pin "1") (pinfunction "1_1") (pintype "passive"))
      (node (ref "C19") (pin "1") (pinfunction "1_1") (pintype "passive"))
      (node (ref "C29") (pin "1") (pinfunction "1_1") (pintype "passive"))
      (node (ref "C32") (pin "1") (pinfunction "1_1") (pintype "passive"))
      (node (ref "C33") (pin "1") (pinfunction "1_1") (pintype "passive"))
      (node (ref "C37") (pin "1") (pinfunction "1_1") (pintype "passive"))
      (node (ref "C41") (pin "1") (pinfunction "1_1") (pintype "passive"))
      (node (ref "C42") (pin "1") (pinfunction "1_1") (pintype "passive"))
      (node (ref "C43") (pin "1") (pinfunction "1_1") (pintype "passive"))
      (node (ref "C44") (pin "1") (pinfunction "1_1") (pintype "passive"))
      (node (ref "C8") (pin "+") (pinfunction "+_+") (pintype "passive"))
      (node (ref "J10") (pin "19") (pinfunction "KL_19") (pintype "passive"))
      (node (ref "J10") (pin "20") (pinfunction "KL_20") (pintype "passive"))
      (node (ref "J11") (pin "19") (pinfunction "KL_19") (pintype "passive"))
      (node (ref "J11") (pin "20") (pinfunction "KL_20") (pintype "passive"))
      (node (ref "J9") (pin "5") (pinfunction "5_5") (pintype "passive"))
      (node (ref "JP1") (pin "2") (pinfunction "S_2") (pintype "passive"))
      (node (ref "LCD1") (pin "2") (pinfunction "VDD_2") (pintype "power_in"))
      (node (ref "R16") (pin "2") (pinfunction "2_2") (pintype "passive"))
      (node (ref "R17") (pin "2") (pinfunction "2_2") (pintype "passive"))
      (node (ref "R18") (pin "2") (pinfunction "2_2") (pintype "passive"))
      (node (ref "R26") (pin "2") (pinfunction "2_2") (pintype "passive"))
      (node (ref "R34") (pin "2") (pinfunction "2_2") (pintype "passive"))
      (node (ref "R45") (pin "2") (pinfunction "2_2") (pintype "passive"))
      (node (ref "R53") (pin "2") (pinfunction "2_2") (pintype "passive"))
      (node (ref "R54") (pin "2") (pinfunction "2_2") (pintype "passive"))
      (node (ref "R55") (pin "2") (pinfunction "2_2") (pintype "passive"))
      (node (ref "R57") (pin "1") (pinfunction "1_1") (pintype "passive"))
      (node (ref "R60") (pin "2") (pinfunction "2_2") (pintype "passive"))
      (node (ref "R8") (pin "2") (pinfunction "2_2") (pintype "passive"))
      (node (ref "U1") (pin "10") (pinfunction "VCC_10") (pintype "power_in"))
      (node (ref "U1") (pin "30") (pinfunction "AVCC_30") (pintype "power_in"))
      (node (ref "U1") (pin "32") (pinfunction "AREF_32") (pintype "passive"))
      (node (ref "U13") (pin "3") (pinfunction "VO_3") (pintype "passive"))
      (node (ref "U2") (pin "4") (pinfunction "V+_4") (pintype "power_in"))
      (node (ref "U3") (pin "14") (pinfunction "VDD_14") (pintype "power_in"))
      (node (ref "U4") (pin "8") (pinfunction "V+_8") (pintype "power_in"))
      (node (ref "U8A") (pin "6") (pinfunction "~{LDAC}_6") (pintype "bidirectional"))
      (node (ref "U8A") (pin "8") (pinfunction "VDD_8") (pintype "bidirectional"))
      (node (ref "U8B") (pin "4") (pinfunction "4_4") (pintype "passive"))
      (node (ref "U8B") (pin "6") (pinfunction "6_6") (pintype "passive"))
      (node (ref "U9") (pin "16") (pinfunction "VCC_16") (pintype "power_in"))
      (node (ref "VR1") (pin "3") (pinfunction "E_3") (pintype "passive"))
      (node (ref "VR2") (pin "3") (pinfunction "E_3") (pintype "passive"))
      (node (ref "VR4") (pin "E") (pinfunction "E_E") (pintype "passive"))
    )
    (net (code "2") (name "+8V") (class "Default")
      (node (ref "C12") (pin "1") (pinfunction "1_1") (pintype "passive"))
      (node (ref "C38") (pin "1") (pinfunction "1_1") (pintype "passive"))
      (node (ref "C39") (pin "2") (pinfunction "2_2") (pintype "passive"))
      (node (ref "C6") (pin "+") (pinfunction "+_+") (pintype "passive"))
      (node (ref "Q3") (pin "3") (pinfunction "S_3") (pintype "passive"))
      (node (ref "R32") (pin "2") (pinfunction "2_2") (pintype "passive"))
      (node (ref "U10") (pin "8") (pinfunction "V+_8") (pintype "power_in"))
      (node (ref "U11") (pin "3") (pinfunction "VO_3") (pintype "passive"))
    )
    (net (code "3") (name "+9V") (class "Default")
      (node (ref "C14") (pin "1") (pinfunction "1_1") (pintype "passive"))
      (node (ref "C40") (pin "2") (pinfunction "2_2") (pintype "passive"))
      (node (ref "C7") (pin "+") (pinfunction "+_+") (pintype "passive"))
      (node (ref "Q6") (pin "3") (pinfunction "S_3") (pintype "passive"))
      (node (ref "R43") (pin "2") (pinfunction "2_2") (pintype "passive"))
      (node (ref "U12") (pin "3") (pinfunction "VO_3") (pintype "passive"))
    )
    (net (code "4") (name "+12V") (class "Default")
      (node (ref "C11") (pin "1") (pinfunction "1_1") (pintype "passive"))
      (node (ref "C13") (pin "1") (pinfunction "1_1") (pintype "passive"))
      (node (ref "C9") (pin "1") (pinfunction "1_1") (pintype "passive"))
      (node (ref "R5") (pin "2") (pinfunction "2_2") (pintype "passive"))
      (node (ref "S5") (pin "1") (pinfunction "O_1") (pintype "passive"))
      (node (ref "U11") (pin "1") (pinfunction "VI_1") (pintype "input"))
      (node (ref "U12") (pin "1") (pinfunction "VI_1") (pintype "input"))
      (node (ref "U13") (pin "1") (pinfunction "VI_1") (pintype "input"))
    )
    (net (code "5") (name "GND") (class "Default")
      (node (ref "C1") (pin "-") (pinfunction "-_-") (pintype "passive"))
      (node (ref "C10") (pin "2") (pinfunction "2_2") (pintype "passive"))
      (node (ref "C11") (pin "2") (pinfunction "2_2") (pintype "passive"))
      (node (ref "C12") (pin "2") (pinfunction "2_2") (pintype "passive"))
      (node (ref "C13") (pin "2") (pinfunction "2_2") (pintype "passive"))
      (node (ref "C14") (pin "2") (pinfunction "2_2") (pintype "passive"))
      (node (ref "C15") (pin "2") (pinfunction "2_2") (pintype "passive"))
      (node (ref "C16") (pin "2") (pinfunction "2_2") (pintype "passive"))
      (node (ref "C17") (pin "2") (pinfunction "2_2") (pintype "passive"))
      (node (ref "C18") (pin "2") (pinfunction "2_2") (pintype "passive"))
      (node (ref "C19") (pin "2") (pinfunction "2_2") (pintype "passive"))
      (node (ref "C2") (pin "2") (pinfunction "2_2") (pintype "passive"))
      (node (ref "C20") (pin "2") (pinfunction "2_2") (pintype "passive"))
      (node (ref "C25") (pin "2") (pinfunction "2_2") (pintype "passive"))
      (node (ref "C27") (pin "2") (pinfunction "2_2") (pintype "passive"))
      (node (ref "C29") (pin "2") (pinfunction "2_2") (pintype "passive"))
      (node (ref "C3") (pin "2") (pinfunction "2_2") (pintype "passive"))
      (node (ref "C30") (pin "2") (pinfunction "2_2") (pintype "passive"))
      (node (ref "C31") (pin "2") (pinfunction "2_2") (pintype "passive"))
      (node (ref "C32") (pin "2") (pinfunction "2_2") (pintype "passive"))
      (node (ref "C34") (pin "2") (pinfunction "2_2") (pintype "passive"))
      (node (ref "C37") (pin "2") (pinfunction "2_2") (pintype "passive"))
      (node (ref "C38") (pin "2") (pinfunction "2_2") (pintype "passive"))
      (node (ref "C4") (pin "-") (pinfunction "-_-") (pintype "passive"))
      (node (ref "C41") (pin "2") (pinfunction "2_2") (pintype "passive"))
      (node (ref "C42") (pin "2") (pinfunction "2_2") (pintype "passive"))
      (node (ref "C43") (pin "2") (pinfunction "2_2") (pintype "passive"))
      (node (ref "C44") (pin "2") (pinfunction "2_2") (pintype "passive"))
      (node (ref "C5") (pin "-") (pinfunction "-_-") (pintype "passive"))
      (node (ref "C6") (pin "-") (pinfunction "-_-") (pintype "passive"))
      (node (ref "C7") (pin "-") (pinfunction "-_-") (pintype "passive"))
      (node (ref "C8") (pin "-") (pinfunction "-_-") (pintype "passive"))
      (node (ref "C9") (pin "2") (pinfunction "2_2") (pintype "passive"))
      (node (ref "J1") (pin "-") (pinfunction "-_-") (pintype "passive"))
      (node (ref "J10") (pin "21") (pinfunction "KL_21") (pintype "passive"))
      (node (ref "J10") (pin "22") (pinfunction "KL_22") (pintype "passive"))
      (node (ref "J10") (pin "23") (pinfunction "KL_23") (pintype "passive"))
      (node (ref "J10") (pin "24") (pinfunction "KL_24") (pintype "passive"))
      (node (ref "J11") (pin "21") (pinfunction "KL_21") (pintype "passive"))
      (node (ref "J11") (pin "22") (pinfunction "KL_22") (pintype "passive"))
      (node (ref "J11") (pin "23") (pinfunction "KL_23") (pintype "passive"))
      (node (ref "J11") (pin "24") (pinfunction "KL_24") (pintype "passive"))
      (node (ref "J2") (pin "1") (pinfunction "1_1") (pintype "passive"))
      (node (ref "J3") (pin "1") (pinfunction "1_1") (pintype "passive"))
      (node (ref "J4") (pin "1") (pinfunction "1_1") (pintype "passive"))
      (node (ref "J5") (pin "1") (pinfunction "1_1") (pintype "passive"))
      (node (ref "J8") (pin "GND@1") (pinfunction "GNDBREAK_GND@1") (pintype "bidirectional"))
      (node (ref "J8") (pin "GND@2") (pinfunction "GND_GND@2") (pintype "bidirectional"))
      (node (ref "J9") (pin "4") (pinfunction "4_4") (pintype "passive"))
      (node (ref "JP1") (pin "6") (pinfunction "S_6") (pintype "passive"))
      (node (ref "LCD1") (pin "1") (pinfunction "VSS_1") (pintype "power_in"))
      (node (ref "LED4") (pin "K") (pinfunction "C_K") (pintype "passive"))
      (node (ref "Q7") (pin "3") (pinfunction "E_3") (pintype "passive"))
      (node (ref "Q8") (pin "3") (pinfunction "E_3") (pintype "passive"))
      (node (ref "R10") (pin "1") (pinfunction "1_1") (pintype "passive"))
      (node (ref "R11") (pin "1") (pinfunction "1_1") (pintype "passive"))
      (node (ref "R19") (pin "1") (pinfunction "1_1") (pintype "passive"))
      (node (ref "R2") (pin "1") (pinfunction "1_1") (pintype "passive"))
      (node (ref "R20") (pin "1") (pinfunction "1_1") (pintype "passive"))
      (node (ref "R21") (pin "1") (pinfunction "1_1") (pintype "passive"))
      (node (ref "R22") (pin "1") (pinfunction "1_1") (pintype "passive"))
      (node (ref "R24") (pin "2") (pinfunction "2_2") (pintype "passive"))
      (node (ref "R27") (pin "2") (pinfunction "2_2") (pintype "passive"))
      (node (ref "R28") (pin "2") (pinfunction "2_2") (pintype "passive"))
      (node (ref "R29") (pin "2") (pinfunction "2_2") (pintype "passive"))
      (node (ref "R30") (pin "1") (pinfunction "1_1") (pintype "passive"))
      (node (ref "R33") (pin "1") (pinfunction "1_1") (pintype "passive"))
      (node (ref "R35") (pin "1") (pinfunction "1_1") (pintype "passive"))
      (node (ref "R37") (pin "1") (pinfunction "1_1") (pintype "passive"))
      (node (ref "R4") (pin "1") (pinfunction "1_1") (pintype "passive"))
      (node (ref "R40") (pin "1") (pinfunction "1_1") (pintype "passive"))
      (node (ref "R44") (pin "1") (pinfunction "1_1") (pintype "passive"))
      (node (ref "R46") (pin "1") (pinfunction "1_1") (pintype "passive"))
      (node (ref "R48") (pin "1") (pinfunction "1_1") (pintype "passive"))
      (node (ref "R51") (pin "1") (pinfunction "1_1") (pintype "passive"))
      (node (ref "R58") (pin "1") (pinfunction "1_1") (pintype "passive"))
      (node (ref "R59") (pin "2") (pinfunction "2_2") (pintype "passive"))
      (node (ref "R6") (pin "1") (pinfunction "1_1") (pintype "passive"))
      (node (ref "S1") (pin "3") (pinfunction "P_3") (pintype "passive"))
      (node (ref "S1") (pin "4") (pinfunction "P_4") (pintype "passive"))
      (node (ref "S2") (pin "3") (pinfunction "P_3") (pintype "passive"))
      (node (ref "S2") (pin "4") (pinfunction "P_4") (pintype "passive"))
      (node (ref "S3") (pin "3") (pinfunction "P_3") (pintype "passive"))
      (node (ref "S3") (pin "4") (pinfunction "P_4") (pintype "passive"))
      (node (ref "S4") (pin "3") (pinfunction "P_3") (pintype "passive"))
      (node (ref "S4") (pin "4") (pinfunction "P_4") (pintype "passive"))
      (node (ref "S5") (pin "B") (pinfunction "B_B") (pintype "passive"))
      (node (ref "S5") (pin "B1") (pinfunction "B1_B1") (pintype "passive"))
      (node (ref "U1") (pin "11") (pinfunction "GND_11") (pintype "power_in"))
      (node (ref "U1") (pin "31") (pinfunction "GND_31") (pintype "power_in"))
      (node (ref "U10") (pin "4") (pinfunction "V-_4") (pintype "power_in"))
      (node (ref "U11") (pin "2") (pinfunction "GND_2") (pintype "passive"))
      (node (ref "U12") (pin "2") (pinfunction "GND_2") (pintype "passive"))
      (node (ref "U13") (pin "2") (pinfunction "GND_2") (pintype "passive"))
      (node (ref "U14") (pin "2") (pinfunction "~{ON}/OFF_2") (pintype "input"))
      (node (ref "U14") (pin "3") (pinfunction "GND_3") (pintype "power_in"))
      (node (ref "U2") (pin "11") (pinfunction "V-_11") (pintype "power_in"))
      (node (ref "U3") (pin "7") (pinfunction "VSS_7") (pintype "power_in"))
      (node (ref "U4") (pin "4") (pinfunction "V-_4") (pintype "power_in"))
      (node (ref "U4") (pin "5") (pinfunction "+IN_5") (pintype "input"))
      (node (ref "U8A") (pin "1") (pinfunction "GND_1") (pintype "bidirectional"))
      (node (ref "U8B") (pin "7") (pinfunction "7_7") (pintype "passive"))
      (node (ref "U9") (pin "15") (pinfunction "GND_15") (pintype "power_in"))
      (node (ref "VR1") (pin "1") (pinfunction "A_1") (pintype "passive"))
      (node (ref "VR1") (pin "CHASSIS2") (pinfunction "P$1_CHASSIS2") (pintype "passive"))
      (node (ref "VR2") (pin "1") (pinfunction "A_1") (pintype "passive"))
      (node (ref "VR2") (pin "CHASSIS2") (pinfunction "P$1_CHASSIS2") (pintype "passive"))
      (node (ref "VR3") (pin "1") (pinfunction "A_1") (pintype "passive"))
      (node (ref "VR3") (pin "1B") (pinfunction "A_1B") (pintype "passive"))
      (node (ref "VR3") (pin "CHASSIS1") (pinfunction "P$1_CHASSIS1") (pintype "passive"))
      (node (ref "VR3") (pin "CHASSIS2") (pinfunction "P$1_CHASSIS2") (pintype "passive"))
      (node (ref "VR4") (pin "A") (pinfunction "A_A") (pintype "passive"))
    )
    (net (code "6") (name "Net-(C20-Pad1)") (class "Default")
      (node (ref "C20") (pin "1") (pinfunction "1_1") (pintype "passive"))
      (node (ref "C21") (pin "1") (pinfunction "1_1") (pintype "passive"))
      (node (ref "R7") (pin "2") (pinfunction "2_2") (pintype "passive"))
      (node (ref "R8") (pin "1") (pinfunction "1_1") (pintype "passive"))
    )
    (net (code "7") (name "Net-(C22-Pad2)") (class "Default")
      (node (ref "C22") (pin "2") (pinfunction "2_2") (pintype "passive"))
      (node (ref "R13") (pin "2") (pinfunction "2_2") (pintype "passive"))
    )
    (net (code "8") (name "Net-(C23-Pad1)") (class "Default")
      (node (ref "C23") (pin "1") (pinfunction "1_1") (pintype "passive"))
      (node (ref "R14") (pin "2") (pinfunction "2_2") (pintype "passive"))
    )
    (net (code "9") (name "Net-(C24-Pad1)") (class "Default")
      (node (ref "C24") (pin "1") (pinfunction "1_1") (pintype "passive"))
      (node (ref "R15") (pin "2") (pinfunction "2_2") (pintype "passive"))
    )
    (net (code "10") (name "Net-(F1-Pad1)") (class "Default")
      (node (ref "F1") (pin "1") (pinfunction "1_1") (pintype "passive"))
      (node (ref "J1") (pin "+") (pinfunction "+_+") (pintype "passive"))
    )
    (net (code "11") (name "Net-(J2-Pad2)") (class "Default")
      (node (ref "J2") (pin "2") (pinfunction "2_2") (pintype "passive"))
      (node (ref "R18") (pin "1") (pinfunction "1_1") (pintype "passive"))
      (node (ref "R19") (pin "2") (pinfunction "2_2") (pintype "passive"))
    )
    (net (code "12") (name "Net-(J4-Pad2)") (class "Default")
      (node (ref "J4") (pin "2") (pinfunction "2_2") (pintype "passive"))
      (node (ref "J4") (pin "5") (pinfunction "5_5") (pintype "passive"))
      (node (ref "R7") (pin "1") (pinfunction "1_1") (pintype "passive"))
    )
    (net (code "13") (name "Net-(J5-Pad2)") (class "Default")
      (node (ref "J5") (pin "2") (pinfunction "2_2") (pintype "passive"))
      (node (ref "R15") (pin "1") (pinfunction "1_1") (pintype "passive"))
    )
    (net (code "14") (name "Net-(J5-Pad5)") (class "Default")
      (node (ref "J5") (pin "5") (pinfunction "5_5") (pintype "passive"))
      (node (ref "R14") (pin "1") (pinfunction "1_1") (pintype "passive"))
    )
    (net (code "15") (name "Net-(J6-Pad1)") (class "Default")
      (node (ref "J6") (pin "1") (pinfunction "1_1") (pintype "passive"))
      (node (ref "TR1") (pin "4") (pinfunction "4_4") (pintype "passive"))
    )
    (net (code "16") (name "Net-(J6-Pad2)") (class "Default")
      (node (ref "J6") (pin "2") (pinfunction "2_2") (pintype "passive"))
      (node (ref "JP6") (pin "2") (pinfunction "2_2") (pintype "passive"))
    )
    (net (code "17") (name "Net-(J6-Pad5)") (class "Default")
      (node (ref "J6") (pin "5") (pinfunction "5_5") (pintype "passive"))
      (node (ref "TR1") (pin "6") (pinfunction "6_6") (pintype "passive"))
    )
    (net (code "18") (name "Net-(J7-Pad1)") (class "Default")
      (node (ref "J7") (pin "1") (pinfunction "1_1") (pintype "passive"))
      (node (ref "TR2") (pin "4") (pinfunction "4_4") (pintype "passive"))
    )
    (net (code "19") (name "Net-(J7-Pad2)") (class "Default")
      (node (ref "J7") (pin "2") (pinfunction "2_2") (pintype "passive"))
      (node (ref "JP7") (pin "2") (pinfunction "2_2") (pintype "passive"))
    )
    (net (code "20") (name "Net-(J7-Pad5)") (class "Default")
      (node (ref "J7") (pin "5") (pinfunction "5_5") (pintype "passive"))
      (node (ref "TR2") (pin "6") (pinfunction "6_6") (pintype "passive"))
    )
    (net (code "21") (name "Net-(J9-Pad2)") (class "Default")
      (node (ref "J9") (pin "2") (pinfunction "2_2") (pintype "passive"))
      (node (ref "R58") (pin "2") (pinfunction "2_2") (pintype "passive"))
      (node (ref "R9") (pin "1") (pinfunction "1_1") (pintype "passive"))
    )
    (net (code "22") (name "Net-(J10A-KL)") (class "Default")
      (node (ref "J10") (pin "1") (pinfunction "KL_1") (pintype "passive"))
      (node (ref "VR3") (pin "3") (pinfunction "E_3") (pintype "passive"))
    )
    (net (code "23") (name "Net-(J10C-KL)") (class "Default")
      (node (ref "J10") (pin "11") (pinfunction "KL_11") (pintype "passive"))
      (node (ref "VR2") (pin "2") (pinfunction "S_2") (pintype "passive"))
    )
    (net (code "24") (name "Net-(J10I-KL)") (class "Default")
      (node (ref "J10") (pin "17") (pinfunction "KL_17") (pintype "passive"))
      (node (ref "LED3") (pin "A") (pinfunction "A_A") (pintype "passive"))
    )
    (net (code "25") (name "Net-(J10R-KL)") (class "Default")
      (node (ref "J10") (pin "3") (pinfunction "KL_3") (pintype "passive"))
      (node (ref "VR3") (pin "3B") (pinfunction "E_3B") (pintype "passive"))
    )
    (net (code "26") (name "Net-(J10T-KL)") (class "Default")
      (node (ref "J10") (pin "5") (pinfunction "KL_5") (pintype "passive"))
      (node (ref "VR3") (pin "2") (pinfunction "S_2") (pintype "passive"))
    )
    (net (code "27") (name "Net-(J10V-KL)") (class "Default")
      (node (ref "J10") (pin "7") (pinfunction "KL_7") (pintype "passive"))
      (node (ref "VR3") (pin "2B") (pinfunction "S_2B") (pintype "passive"))
    )
    (net (code "28") (name "Net-(J10X-KL)") (class "Default")
      (node (ref "J10") (pin "9") (pinfunction "KL_9") (pintype "passive"))
      (node (ref "VR1") (pin "2") (pinfunction "S_2") (pintype "passive"))
    )
    (net (code "29") (name "Net-(JP6-Pad1)") (class "Default")
      (node (ref "JP6") (pin "1") (pinfunction "1_1") (pintype "passive"))
      (node (ref "TR1") (pin "5") (pinfunction "5_5") (pintype "passive"))
    )
    (net (code "30") (name "Net-(JP7-Pad1)") (class "Default")
      (node (ref "JP7") (pin "1") (pinfunction "1_1") (pintype "passive"))
      (node (ref "TR2") (pin "5") (pinfunction "5_5") (pintype "passive"))
    )
    (net (code "31") (name "Net-(LCD1-A)") (class "Default")
      (node (ref "LCD1") (pin "15") (pinfunction "A_15") (pintype "input"))
      (node (ref "R55") (pin "1") (pinfunction "1_1") (pintype "passive"))
    )
    (net (code "32") (name "Net-(LCD1-K)") (class "Default")
      (node (ref "LCD1") (pin "16") (pinfunction "K_16") (pintype "input"))
      (node (ref "Q8") (pin "1") (pinfunction "C_1") (pintype "passive"))
    )
    (net (code "33") (name "Net-(LCD1-VO)") (class "Default")
      (node (ref "LCD1") (pin "3") (pinfunction "VO_3") (pintype "input"))
      (node (ref "VR4") (pin "S") (pinfunction "S_S") (pintype "passive"))
    )
    (net (code "34") (name "Net-(LED1-PadA)") (class "Default")
      (node (ref "LED1") (pin "A") (pinfunction "A_A") (pintype "passive"))
      (node (ref "R54") (pin "1") (pinfunction "1_1") (pintype "passive"))
    )
    (net (code "35") (name "Net-(LED2-PadA)") (class "Default")
      (node (ref "LED2") (pin "A") (pinfunction "A_A") (pintype "passive"))
      (node (ref "R53") (pin "1") (pinfunction "1_1") (pintype "passive"))
    )
    (net (code "36") (name "Net-(LED3-C)") (class "Default")
      (node (ref "LED3") (pin "K") (pinfunction "C_K") (pintype "passive"))
      (node (ref "R59") (pin "1") (pinfunction "1_1") (pintype "passive"))
    )
    (net (code "37") (name "Net-(LED4-PadA)") (class "Default")
      (node (ref "LED4") (pin "A") (pinfunction "A_A") (pintype "passive"))
      (node (ref "R60") (pin "1") (pinfunction "1_1") (pintype "passive"))
    )
    (net (code "38") (name "Net-(Q1-D)") (class "Default")
      (node (ref "Q1") (pin "2") (pinfunction "D_2") (pintype "passive"))
      (node (ref "TR1") (pin "1") (pinfunction "1_1") (pintype "passive"))
    )
    (net (code "39") (name "Net-(Q1-G)") (class "Default")
      (node (ref "Q1") (pin "1") (pinfunction "G_1") (pintype "passive"))
      (node (ref "R38") (pin "2") (pinfunction "2_2") (pintype "passive"))
    )
    (net (code "40") (name "Net-(Q2-D)") (class "Default")
      (node (ref "Q2") (pin "2") (pinfunction "D_2") (pintype "passive"))
      (node (ref "TR1") (pin "3") (pinfunction "3_3") (pintype "passive"))
    )
    (net (code "41") (name "Net-(Q2-G)") (class "Default")
      (node (ref "Q2") (pin "1") (pinfunction "G_1") (pintype "passive"))
      (node (ref "R41") (pin "2") (pinfunction "2_2") (pintype "passive"))
    )
    (net (code "42") (name "Net-(Q3-D)") (class "Default")
      (node (ref "Q3") (pin "2") (pinfunction "D_2") (pintype "passive"))
      (node (ref "TR1") (pin "2") (pinfunction "2_2") (pintype "passive"))
    )
    (net (code "43") (name "Net-(Q3-G)") (class "Default")
      (node (ref "C39") (pin "1") (pinfunction "1_1") (pintype "passive"))
      (node (ref "Q3") (pin "1") (pinfunction "G_1") (pintype "passive"))
      (node (ref "R39") (pin "2") (pinfunction "2_2") (pintype "passive"))
    )
    (net (code "44") (name "Net-(Q4-D)") (class "Default")
      (node (ref "Q4") (pin "2") (pinfunction "D_2") (pintype "passive"))
      (node (ref "TR2") (pin "1") (pinfunction "1_1") (pintype "passive"))
    )
    (net (code "45") (name "Net-(Q4-G)") (class "Default")
      (node (ref "Q4") (pin "1") (pinfunction "G_1") (pintype "passive"))
      (node (ref "R49") (pin "2") (pinfunction "2_2") (pintype "passive"))
    )
    (net (code "46") (name "Net-(Q5-D)") (class "Default")
      (node (ref "Q5") (pin "2") (pinfunction "D_2") (pintype "passive"))
      (node (ref "TR2") (pin "3") (pinfunction "3_3") (pintype "passive"))
    )
    (net (code "47") (name "Net-(Q5-G)") (class "Default")
      (node (ref "Q5") (pin "1") (pinfunction "G_1") (pintype "passive"))
      (node (ref "R52") (pin "2") (pinfunction "2_2") (pintype "passive"))
    )
    (net (code "48") (name "Net-(Q6-D)") (class "Default")
      (node (ref "Q6") (pin "2") (pinfunction "D_2") (pintype "passive"))
      (node (ref "TR2") (pin "2") (pinfunction "2_2") (pintype "passive"))
    )
    (net (code "49") (name "Net-(Q6-G)") (class "Default")
      (node (ref "C40") (pin "1") (pinfunction "1_1") (pintype "passive"))
      (node (ref "Q6") (pin "1") (pinfunction "G_1") (pintype "passive"))
      (node (ref "R50") (pin "2") (pinfunction "2_2") (pintype "passive"))
    )
    (net (code "50") (name "Net-(Q7-B)") (class "Default")
      (node (ref "Q7") (pin "2") (pinfunction "B_2") (pintype "passive"))
      (node (ref "R56") (pin "1") (pinfunction "1_1") (pintype "passive"))
    )
    (net (code "51") (name "Net-(Q7-C)") (class "Default")
      (node (ref "Q7") (pin "1") (pinfunction "C_1") (pintype "passive"))
      (node (ref "Q8") (pin "2") (pinfunction "B_2") (pintype "passive"))
      (node (ref "R57") (pin "2") (pinfunction "2_2") (pintype "passive"))
    )
    (net (code "52") (name "Net-(S5-P)") (class "Default")
      (node (ref "C5") (pin "+") (pinfunction "+_+") (pintype "passive"))
      (node (ref "D1") (pin "C") (pinfunction "C_C") (pintype "passive"))
      (node (ref "F1") (pin "2") (pinfunction "2_2") (pintype "passive"))
      (node (ref "S5") (pin "2") (pinfunction "P_2") (pintype "passive"))
      (node (ref "S5") (pin "3") (pinfunction "S_3") (pintype "passive"))
    )
    (net (code "53") (name "Net-(U1-(ADC2)PA2)") (class "Default")
      (node (ref "R3") (pin "1") (pinfunction "1_1") (pintype "passive"))
      (node (ref "R4") (pin "2") (pinfunction "2_2") (pintype "passive"))
      (node (ref "U1") (pin "38") (pinfunction "(ADC2)PA2_38") (pintype "bidirectional"))
    )
    (net (code "54") (name "Net-(U1-(ADC3)PA3)") (class "Default")
      (node (ref "R5") (pin "1") (pinfunction "1_1") (pintype "passive"))
      (node (ref "R6") (pin "2") (pinfunction "2_2") (pintype "passive"))
      (node (ref "U1") (pin "37") (pinfunction "(ADC3)PA3_37") (pintype "bidirectional"))
    )
    (net (code "55") (name "Net-(U1-XTAL1)") (class "Default")
      (node (ref "C16") (pin "1") (pinfunction "1_1") (pintype "passive"))
      (node (ref "U1") (pin "13") (pinfunction "XTAL1_13") (pintype "bidirectional"))
      (node (ref "XTAL1") (pin "2") (pinfunction "2_2") (pintype "passive"))
    )
    (net (code "56") (name "Net-(U1-XTAL2)") (class "Default")
      (node (ref "C15") (pin "1") (pinfunction "1_1") (pintype "passive"))
      (node (ref "U1") (pin "12") (pinfunction "XTAL2_12") (pintype "bidirectional"))
      (node (ref "XTAL1") (pin "1") (pinfunction "1_1") (pintype "passive"))
    )
    (net (code "57") (name "Net-(U2A-+IN)") (class "Default")
      (node (ref "C28") (pin "2") (pinfunction "2_2") (pintype "passive"))
      (node (ref "J2") (pin "5") (pinfunction "5_5") (pintype "passive"))
      (node (ref "R21") (pin "2") (pinfunction "2_2") (pintype "passive"))
      (node (ref "U2") (pin "3") (pinfunction "+IN_3") (pintype "input"))
    )
    (net (code "58") (name "Net-(U2A--IN)") (class "Default")
      (node (ref "R24") (pin "1") (pinfunction "1_1") (pintype "passive"))
      (node (ref "R25") (pin "1") (pinfunction "1_1") (pintype "passive"))
      (node (ref "U2") (pin "2") (pinfunction "-IN_2") (pintype "input"))
    )
    (net (code "59") (name "Net-(U2A-OUT)") (class "Default")
      (node (ref "D2") (pin "A") (pinfunction "A_A") (pintype "passive"))
      (node (ref "R25") (pin "2") (pinfunction "2_2") (pintype "passive"))
      (node (ref "U2") (pin "1") (pinfunction "OUT_1") (pintype "output"))
      (node (ref "U2") (pin "12") (pinfunction "+IN_12") (pintype "input"))
    )
    (net (code "60") (name "Net-(U2B-+IN)") (class "Default")
      (node (ref "C26") (pin "2") (pinfunction "2_2") (pintype "passive"))
      (node (ref "R20") (pin "2") (pinfunction "2_2") (pintype "passive"))
      (node (ref "U2") (pin "5") (pinfunction "+IN_5") (pintype "input"))
    )
    (net (code "61") (name "Net-(U2B--IN)") (class "Default")
      (node (ref "R22") (pin "2") (pinfunction "2_2") (pintype "passive"))
      (node (ref "R23") (pin "1") (pinfunction "1_1") (pintype "passive"))
      (node (ref "U2") (pin "6") (pinfunction "-IN_6") (pintype "input"))
    )
    (net (code "62") (name "Net-(U2B-OUT)") (class "Default")
      (node (ref "D3") (pin "A") (pinfunction "A_A") (pintype "passive"))
      (node (ref "R23") (pin "2") (pinfunction "2_2") (pintype "passive"))
      (node (ref "U2") (pin "10") (pinfunction "+IN_10") (pintype "input"))
      (node (ref "U2") (pin "7") (pinfunction "OUT_7") (pintype "output"))
    )
    (net (code "63") (name "Net-(U2C--IN)") (class "Default")
      (node (ref "R26") (pin "1") (pinfunction "1_1") (pintype "passive"))
      (node (ref "R27") (pin "1") (pinfunction "1_1") (pintype "passive"))
      (node (ref "U2") (pin "13") (pinfunction "-IN_13") (pintype "input"))
      (node (ref "U2") (pin "9") (pinfunction "-IN_9") (pintype "input"))
    )
    (net (code "64") (name "Net-(U3A-A)") (class "Default")
      (node (ref "S2") (pin "1") (pinfunction "S_1") (pintype "passive"))
      (node (ref "S2") (pin "2") (pinfunction "S_2") (pintype "passive"))
      (node (ref "U3") (pin "1") (pinfunction "A_1") (pintype "tri_state"))
    )
    (net (code "65") (name "Net-(U3B-A)") (class "Default")
      (node (ref "S4") (pin "1") (pinfunction "S_1") (pintype "passive"))
      (node (ref "S4") (pin "2") (pinfunction "S_2") (pintype "passive"))
      (node (ref "U3") (pin "4") (pinfunction "A_4") (pintype "tri_state"))
    )
    (net (code "66") (name "Net-(U3C-A)") (class "Default")
      (node (ref "S1") (pin "1") (pinfunction "S_1") (pintype "passive"))
      (node (ref "S1") (pin "2") (pinfunction "S_2") (pintype "passive"))
      (node (ref "U3") (pin "8") (pinfunction "A_8") (pintype "tri_state"))
    )
    (net (code "67") (name "Net-(U3D-A)") (class "Default")
      (node (ref "S3") (pin "1") (pinfunction "S_1") (pintype "passive"))
      (node (ref "S3") (pin "2") (pinfunction "S_2") (pintype "passive"))
      (node (ref "U3") (pin "11") (pinfunction "A_11") (pintype "tri_state"))
    )
    (net (code "68") (name "Net-(U4A-+IN)") (class "Default")
      (node (ref "C21") (pin "2") (pinfunction "2_2") (pintype "passive"))
      (node (ref "R10") (pin "2") (pinfunction "2_2") (pintype "passive"))
      (node (ref "U4") (pin "3") (pinfunction "+IN_3") (pintype "input"))
    )
    (net (code "69") (name "Net-(U4A--IN)") (class "Default")
      (node (ref "R11") (pin "2") (pinfunction "2_2") (pintype "passive"))
      (node (ref "R12") (pin "1") (pinfunction "1_1") (pintype "passive"))
      (node (ref "U4") (pin "2") (pinfunction "-IN_2") (pintype "input"))
    )
    (net (code "70") (name "Net-(U4A-OUT)") (class "Default")
      (node (ref "R12") (pin "2") (pinfunction "2_2") (pintype "passive"))
      (node (ref "R13") (pin "1") (pinfunction "1_1") (pintype "passive"))
      (node (ref "U4") (pin "1") (pinfunction "OUT_1") (pintype "output"))
      (node (ref "U4") (pin "6") (pinfunction "-IN_6") (pintype "input"))
    )
    (net (code "71") (name "Net-(U8A-OUTA)") (class "Default")
      (node (ref "R31") (pin "1") (pinfunction "1_1") (pintype "passive"))
      (node (ref "U8A") (pin "2") (pinfunction "OUTA_2") (pintype "bidirectional"))
      (node (ref "U8B") (pin "5") (pinfunction "5_5") (pintype "passive"))
    )
    (net (code "72") (name "Net-(U8A-OUTB)") (class "Default")
      (node (ref "R42") (pin "1") (pinfunction "1_1") (pintype "passive"))
      (node (ref "U8A") (pin "7") (pinfunction "OUTB_7") (pintype "bidirectional"))
      (node (ref "U8B") (pin "8") (pinfunction "8_8") (pintype "passive"))
    )
    (net (code "73") (name "Net-(U9A-C1+)") (class "Default")
      (node (ref "C35") (pin "1") (pinfunction "1_1") (pintype "passive"))
      (node (ref "U9") (pin "1") (pinfunction "C1+_1") (pintype "bidirectional"))
    )
    (net (code "74") (name "Net-(U9A-C1-)") (class "Default")
      (node (ref "C35") (pin "2") (pinfunction "2_2") (pintype "passive"))
      (node (ref "U9") (pin "3") (pinfunction "C1-_3") (pintype "bidirectional"))
    )
    (net (code "75") (name "Net-(U9A-C2+)") (class "Default")
      (node (ref "C36") (pin "1") (pinfunction "1_1") (pintype "passive"))
      (node (ref "U9") (pin "4") (pinfunction "C2+_4") (pintype "bidirectional"))
    )
    (net (code "76") (name "Net-(U9A-C2-)") (class "Default")
      (node (ref "C36") (pin "2") (pinfunction "2_2") (pintype "passive"))
      (node (ref "U9") (pin "5") (pinfunction "C2-_5") (pintype "bidirectional"))
    )
    (net (code "77") (name "Net-(U9A-R1IN)") (class "Default")
      (node (ref "J3") (pin "2") (pinfunction "2_2") (pintype "passive"))
      (node (ref "U9") (pin "13") (pinfunction "R1IN_13") (pintype "input"))
    )
    (net (code "78") (name "Net-(U9A-R2IN)") (class "Default")
      (node (ref "J3") (pin "4") (pinfunction "4_4") (pintype "passive"))
      (node (ref "U9") (pin "8") (pinfunction "R2IN_8") (pintype "input"))
    )
    (net (code "79") (name "Net-(U9A-R2OUT)") (class "Default")
      (node (ref "R9") (pin "2") (pinfunction "2_2") (pintype "passive"))
      (node (ref "U9") (pin "9") (pinfunction "R2OUT_9") (pintype "output"))
    )
    (net (code "80") (name "Net-(U9A-T1OUT)") (class "Default")
      (node (ref "J3") (pin "5") (pinfunction "5_5") (pintype "passive"))
      (node (ref "U9") (pin "14") (pinfunction "T1OUT_14") (pintype "output"))
    )
    (net (code "81") (name "Net-(U9A-T2IN)") (class "Default")
      (node (ref "J9") (pin "3") (pinfunction "3_3") (pintype "passive"))
      (node (ref "U9") (pin "10") (pinfunction "T2IN_10") (pintype "input"))
    )
    (net (code "82") (name "Net-(U9A-T2OUT)") (class "Default")
      (node (ref "J3") (pin "3") (pinfunction "3_3") (pintype "passive"))
      (node (ref "U9") (pin "7") (pinfunction "T2OUT_7") (pintype "output"))
    )
    (net (code "83") (name "Net-(U9A-V+)") (class "Default")
      (node (ref "C33") (pin "2") (pinfunction "2_2") (pintype "passive"))
      (node (ref "U9") (pin "2") (pinfunction "V+_2") (pintype "bidirectional"))
    )
    (net (code "84") (name "Net-(U9A-V-)") (class "Default")
      (node (ref "C34") (pin "1") (pinfunction "1_1") (pintype "passive"))
      (node (ref "U9") (pin "6") (pinfunction "V-_6") (pintype "bidirectional"))
    )
    (net (code "85") (name "Net-(U10A-+IN)") (class "Default")
      (node (ref "R31") (pin "2") (pinfunction "2_2") (pintype "passive"))
      (node (ref "R32") (pin "1") (pinfunction "1_1") (pintype "passive"))
      (node (ref "R33") (pin "2") (pinfunction "2_2") (pintype "passive"))
      (node (ref "U10") (pin "3") (pinfunction "+IN_3") (pintype "input"))
    )
    (net (code "86") (name "Net-(U10A--IN)") (class "Default")
      (node (ref "R34") (pin "1") (pinfunction "1_1") (pintype "passive"))
      (node (ref "R35") (pin "2") (pinfunction "2_2") (pintype "passive"))
      (node (ref "R36") (pin "1") (pinfunction "1_1") (pintype "passive"))
      (node (ref "U10") (pin "2") (pinfunction "-IN_2") (pintype "input"))
    )
    (net (code "87") (name "Net-(U10A-OUT)") (class "Default")
      (node (ref "R36") (pin "2") (pinfunction "2_2") (pintype "passive"))
      (node (ref "R39") (pin "1") (pinfunction "1_1") (pintype "passive"))
      (node (ref "U10") (pin "1") (pinfunction "OUT_1") (pintype "output"))
    )
    (net (code "88") (name "Net-(U10B-+IN)") (class "Default")
      (node (ref "R42") (pin "2") (pinfunction "2_2") (pintype "passive"))
      (node (ref "R43") (pin "1") (pinfunction "1_1") (pintype "passive"))
      (node (ref "R44") (pin "2") (pinfunction "2_2") (pintype "passive"))
      (node (ref "U10") (pin "5") (pinfunction "+IN_5") (pintype "input"))
    )
    (net (code "89") (name "Net-(U10B--IN)") (class "Default")
      (node (ref "R45") (pin "1") (pinfunction "1_1") (pintype "passive"))
      (node (ref "R46") (pin "2") (pinfunction "2_2") (pintype "passive"))
      (node (ref "R47") (pin "1") (pinfunction "1_1") (pintype "passive"))
      (node (ref "U10") (pin "6") (pinfunction "-IN_6") (pintype "input"))
    )
    (net (code "90") (name "Net-(U10B-OUT)") (class "Default")
      (node (ref "R47") (pin "2") (pinfunction "2_2") (pintype "passive"))
      (node (ref "R50") (pin "1") (pinfunction "1_1") (pintype "passive"))
      (node (ref "U10") (pin "7") (pinfunction "OUT_7") (pintype "output"))
    )
    (net (code "91") (name "Net-(U14-ADJ)") (class "Default")
      (node (ref "R1") (pin "1") (pinfunction "1_1") (pintype "passive"))
      (node (ref "R2") (pin "2") (pinfunction "2_2") (pintype "passive"))
      (node (ref "U14") (pin "1") (pinfunction "ADJ_1") (pintype "passive"))
    )
    (net (code "92") (name "Net-(U14-OUT)") (class "Default")
      (node (ref "C3") (pin "1") (pinfunction "1_1") (pintype "passive"))
      (node (ref "C4") (pin "+") (pinfunction "+_+") (pintype "passive"))
      (node (ref "D1") (pin "A") (pinfunction "A_A") (pintype "passive"))
      (node (ref "R1") (pin "2") (pinfunction "2_2") (pintype "passive"))
      (node (ref "U14") (pin "5") (pinfunction "OUT_5") (pintype "passive"))
    )
    (net (code "93") (name "PA0") (class "Default")
      (node (ref "Q1") (pin "3") (pinfunction "S_3") (pintype "passive"))
      (node (ref "Q2") (pin "3") (pinfunction "S_3") (pintype "passive"))
      (node (ref "Q4") (pin "3") (pinfunction "S_3") (pintype "passive"))
      (node (ref "Q5") (pin "3") (pinfunction "S_3") (pintype "passive"))
      (node (ref "R30") (pin "2") (pinfunction "2_2") (pintype "passive"))
      (node (ref "U1") (pin "40") (pinfunction "(ADC0)PA0_40") (pintype "bidirectional"))
    )
    (net (code "94") (name "PA1") (class "Default")
      (node (ref "C25") (pin "1") (pinfunction "1_1") (pintype "passive"))
      (node (ref "C26") (pin "1") (pinfunction "1_1") (pintype "passive"))
      (node (ref "J11") (pin "5") (pinfunction "KL_5") (pintype "passive"))
      (node (ref "U1") (pin "39") (pinfunction "(ADC1)PA1_39") (pintype "bidirectional"))
    )
    (net (code "95") (name "PA4") (class "Default")
      (node (ref "J11") (pin "9") (pinfunction "KL_9") (pintype "passive"))
      (node (ref "U1") (pin "36") (pinfunction "(ADC4)PA4_36") (pintype "bidirectional"))
    )
    (net (code "96") (name "PA5") (class "Default")
      (node (ref "J11") (pin "11") (pinfunction "KL_11") (pintype "passive"))
      (node (ref "U1") (pin "35") (pinfunction "(ADC5)PA5_35") (pintype "bidirectional"))
    )
    (net (code "97") (name "PA6") (class "Default")
      (node (ref "C31") (pin "1") (pinfunction "1_1") (pintype "passive"))
      (node (ref "D2") (pin "C") (pinfunction "C_C") (pintype "passive"))
      (node (ref "R29") (pin "1") (pinfunction "1_1") (pintype "passive"))
      (node (ref "U1") (pin "34") (pinfunction "(ADC6)PA6_34") (pintype "bidirectional"))
    )
    (net (code "98") (name "PA7") (class "Default")
      (node (ref "C30") (pin "1") (pinfunction "1_1") (pintype "passive"))
      (node (ref "D3") (pin "C") (pinfunction "C_C") (pintype "passive"))
      (node (ref "R28") (pin "1") (pinfunction "1_1") (pintype "passive"))
      (node (ref "U1") (pin "33") (pinfunction "(ADC7)PA7_33") (pintype "bidirectional"))
    )
    (net (code "99") (name "PB0") (class "Default")
      (node (ref "R48") (pin "2") (pinfunction "2_2") (pintype "passive"))
      (node (ref "R49") (pin "1") (pinfunction "1_1") (pintype "passive"))
      (node (ref "U1") (pin "1") (pinfunction "(T0/XCK)PB0_1") (pintype "bidirectional"))
    )
    (net (code "100") (name "PB1") (class "Default")
      (node (ref "R51") (pin "2") (pinfunction "2_2") (pintype "passive"))
      (node (ref "R52") (pin "1") (pinfunction "1_1") (pintype "passive"))
      (node (ref "U1") (pin "2") (pinfunction "(T1)PB1_2") (pintype "bidirectional"))
    )
    (net (code "101") (name "PB2") (class "Default")
      (node (ref "R37") (pin "2") (pinfunction "2_2") (pintype "passive"))
      (node (ref "R38") (pin "1") (pinfunction "1_1") (pintype "passive"))
      (node (ref "U1") (pin "3") (pinfunction "(AIN0/INT2)PB2_3") (pintype "bidirectional"))
    )
    (net (code "102") (name "PB3") (class "Default")
      (node (ref "R40") (pin "2") (pinfunction "2_2") (pintype "passive"))
      (node (ref "R41") (pin "1") (pinfunction "1_1") (pintype "passive"))
      (node (ref "U1") (pin "4") (pinfunction "(AIN1/OC0)PB3_4") (pintype "bidirectional"))
    )
    (net (code "103") (name "PB5") (class "Default")
      (node (ref "JP1") (pin "4") (pinfunction "S_4") (pintype "passive"))
      (node (ref "U1") (pin "6") (pinfunction "(MOSI)PB5_6") (pintype "bidirectional"))
      (node (ref "U8A") (pin "4") (pinfunction "DIN_4") (pintype "bidirectional"))
      (node (ref "U8B") (pin "3") (pinfunction "3_3") (pintype "passive"))
    )
    (net (code "104") (name "PB6") (class "Default")
      (node (ref "JP1") (pin "1") (pinfunction "S_1") (pintype "passive"))
      (node (ref "U1") (pin "7") (pinfunction "(MISO)PB6_7") (pintype "bidirectional"))
    )
    (net (code "105") (name "PB7") (class "Default")
      (node (ref "JP1") (pin "3") (pinfunction "S_3") (pintype "passive"))
      (node (ref "U1") (pin "8") (pinfunction "(SCK)PB7_8") (pintype "bidirectional"))
      (node (ref "U8A") (pin "5") (pinfunction "SCLK_5") (pintype "bidirectional"))
      (node (ref "U8B") (pin "2") (pinfunction "2_2") (pintype "passive"))
    )
    (net (code "106") (name "PC0") (class "Default")
      (node (ref "J10") (pin "2") (pinfunction "KL_2") (pintype "passive"))
      (node (ref "J11") (pin "2") (pinfunction "KL_2") (pintype "passive"))
      (node (ref "U1") (pin "22") (pinfunction "(SCL)PC0_22") (pintype "bidirectional"))
      (node (ref "U3") (pin "12") (pinfunction "C_12") (pintype "input"))
      (node (ref "U3") (pin "13") (pinfunction "C_13") (pintype "input"))
      (node (ref "U3") (pin "5") (pinfunction "C_5") (pintype "input"))
      (node (ref "U3") (pin "6") (pinfunction "C_6") (pintype "input"))
    )
    (net (code "107") (name "PC1") (class "Default")
      (node (ref "J10") (pin "4") (pinfunction "KL_4") (pintype "passive"))
      (node (ref "J11") (pin "4") (pinfunction "KL_4") (pintype "passive"))
      (node (ref "LCD1") (pin "5") (pinfunction "RW_5") (pintype "input"))
      (node (ref "U1") (pin "23") (pinfunction "(SDA)PC1_23") (pintype "bidirectional"))
    )
    (net (code "108") (name "PC2") (class "Default")
      (node (ref "J10") (pin "6") (pinfunction "KL_6") (pintype "passive"))
      (node (ref "J11") (pin "6") (pinfunction "KL_6") (pintype "passive"))
      (node (ref "LCD1") (pin "6") (pinfunction "E_6") (pintype "input"))
      (node (ref "U1") (pin "24") (pinfunction "(TCK)PC2_24") (pintype "bidirectional"))
    )
    (net (code "109") (name "PC3") (class "Default")
      (node (ref "J10") (pin "8") (pinfunction "KL_8") (pintype "passive"))
      (node (ref "J11") (pin "8") (pinfunction "KL_8") (pintype "passive"))
      (node (ref "LCD1") (pin "4") (pinfunction "RS_4") (pintype "input"))
      (node (ref "U1") (pin "25") (pinfunction "(TMS)PC3_25") (pintype "bidirectional"))
    )
    (net (code "110") (name "PC4") (class "Default")
      (node (ref "J10") (pin "10") (pinfunction "KL_10") (pintype "passive"))
      (node (ref "J11") (pin "10") (pinfunction "KL_10") (pintype "passive"))
      (node (ref "LCD1") (pin "11") (pinfunction "DB4_11") (pintype "bidirectional"))
      (node (ref "U1") (pin "26") (pinfunction "(TDO)PC4_26") (pintype "bidirectional"))
      (node (ref "U3") (pin "10") (pinfunction "B_10") (pintype "tri_state"))
    )
    (net (code "111") (name "PC5") (class "Default")
      (node (ref "J10") (pin "12") (pinfunction "KL_12") (pintype "passive"))
      (node (ref "J11") (pin "12") (pinfunction "KL_12") (pintype "passive"))
      (node (ref "LCD1") (pin "12") (pinfunction "DB5_12") (pintype "bidirectional"))
      (node (ref "U1") (pin "27") (pinfunction "(TDI)PC5_27") (pintype "bidirectional"))
      (node (ref "U3") (pin "9") (pinfunction "B_9") (pintype "tri_state"))
    )
    (net (code "112") (name "PC6") (class "Default")
      (node (ref "J10") (pin "14") (pinfunction "KL_14") (pintype "passive"))
      (node (ref "J11") (pin "14") (pinfunction "KL_14") (pintype "passive"))
      (node (ref "LCD1") (pin "13") (pinfunction "DB6_13") (pintype "bidirectional"))
      (node (ref "U1") (pin "28") (pinfunction "(TOSC1)PC6_28") (pintype "bidirectional"))
      (node (ref "U3") (pin "3") (pinfunction "B_3") (pintype "tri_state"))
    )
    (net (code "113") (name "PC7") (class "Default")
      (node (ref "J10") (pin "16") (pinfunction "KL_16") (pintype "passive"))
      (node (ref "J11") (pin "16") (pinfunction "KL_16") (pintype "passive"))
      (node (ref "LCD1") (pin "14") (pinfunction "DB7_14") (pintype "bidirectional"))
      (node (ref "U1") (pin "29") (pinfunction "(TOSC2)PC7_29") (pintype "bidirectional"))
      (node (ref "U3") (pin "2") (pinfunction "B_2") (pintype "tri_state"))
    )
    (net (code "114") (name "PD0") (class "Default")
      (node (ref "U1") (pin "14") (pinfunction "(RXD)PD0_14") (pintype "bidirectional"))
      (node (ref "U9") (pin "12") (pinfunction "R1OUT_12") (pintype "output"))
    )
    (net (code "115") (name "PD1") (class "Default")
      (node (ref "U1") (pin "15") (pinfunction "(TXD)PD1_15") (pintype "bidirectional"))
      (node (ref "U9") (pin "11") (pinfunction "T1IN_11") (pintype "input"))
    )
    (net (code "116") (name "PD2") (class "Default")
      (node (ref "U1") (pin "16") (pinfunction "(INT0)PD2_16") (pintype "bidirectional"))
      (node (ref "U2") (pin "14") (pinfunction "OUT_14") (pintype "output"))
    )
    (net (code "117") (name "PD3") (class "Default")
      (node (ref "U1") (pin "17") (pinfunction "(INT1)PD3_17") (pintype "bidirectional"))
      (node (ref "U2") (pin "8") (pinfunction "OUT_8") (pintype "output"))
    )
    (net (code "118") (name "PD5") (class "Default")
      (node (ref "J10") (pin "15") (pinfunction "KL_15") (pintype "passive"))
      (node (ref "J11") (pin "15") (pinfunction "KL_15") (pintype "passive"))
      (node (ref "LED2") (pin "K") (pinfunction "C_K") (pintype "passive"))
      (node (ref "U1") (pin "19") (pinfunction "(OC1A)PD5_19") (pintype "bidirectional"))
    )
    (net (code "119") (name "PD6") (class "Default")
      (node (ref "J10") (pin "13") (pinfunction "KL_13") (pintype "passive"))
      (node (ref "J11") (pin "13") (pinfunction "KL_13") (pintype "passive"))
      (node (ref "LED1") (pin "K") (pinfunction "C_K") (pintype "passive"))
      (node (ref "U1") (pin "20") (pinfunction "(ICP)PD6_20") (pintype "bidirectional"))
    )
    (net (code "120") (name "PD7") (class "Default")
      (node (ref "J10") (pin "18") (pinfunction "KL_18") (pintype "passive"))
      (node (ref "J11") (pin "18") (pinfunction "KL_18") (pintype "passive"))
      (node (ref "R56") (pin "2") (pinfunction "2_2") (pintype "passive"))
      (node (ref "U1") (pin "21") (pinfunction "(OC2)PD7_21") (pintype "bidirectional"))
    )
    (net (code "121") (name "RB4") (class "Default")
      (node (ref "C27") (pin "1") (pinfunction "1_1") (pintype "passive"))
      (node (ref "C28") (pin "1") (pinfunction "1_1") (pintype "passive"))
      (node (ref "J11") (pin "7") (pinfunction "KL_7") (pintype "passive"))
    )
    (net (code "122") (name "RB9") (class "Default")
      (node (ref "C22") (pin "1") (pinfunction "1_1") (pintype "passive"))
      (node (ref "C24") (pin "2") (pinfunction "2_2") (pintype "passive"))
      (node (ref "J11") (pin "3") (pinfunction "KL_3") (pintype "passive"))
      (node (ref "R17") (pin "1") (pinfunction "1_1") (pintype "passive"))
    )
    (net (code "123") (name "RB10") (class "Default")
      (node (ref "C23") (pin "2") (pinfunction "2_2") (pintype "passive"))
      (node (ref "J11") (pin "1") (pinfunction "KL_1") (pintype "passive"))
      (node (ref "R16") (pin "1") (pinfunction "1_1") (pintype "passive"))
    )
    (net (code "124") (name "RESET") (class "Default")
      (node (ref "JP1") (pin "5") (pinfunction "S_5") (pintype "passive"))
      (node (ref "U1") (pin "9") (pinfunction "RESET_9") (pintype "input"))
    )
    (net (code "125") (name "STATE") (class "Default")
      (node (ref "J11") (pin "17") (pinfunction "KL_17") (pintype "passive"))
      (node (ref "J9") (pin "1") (pinfunction "1_1") (pintype "passive"))
    )
    (net (code "126") (name "V+") (class "Default")
      (node (ref "C1") (pin "+") (pinfunction "+_+") (pintype "passive"))
      (node (ref "C2") (pin "1") (pinfunction "1_1") (pintype "passive"))
      (node (ref "J8") (pin "PWR") (pinfunction "PWR_PWR") (pintype "bidirectional"))
      (node (ref "R3") (pin "2") (pinfunction "2_2") (pintype "passive"))
      (node (ref "U14") (pin "4") (pinfunction "IN_4") (pintype "passive"))
    )
    (net (code "127") (name "unconnected-(J2-Pad3)") (class "Default")
      (node (ref "J2") (pin "3") (pinfunction "3_3") (pintype "passive"))
    )
    (net (code "128") (name "unconnected-(J2-Pad4)") (class "Default")
      (node (ref "J2") (pin "4") (pinfunction "4_4") (pintype "passive"))
    )
    (net (code "129") (name "unconnected-(J4-Pad3)") (class "Default")
      (node (ref "J4") (pin "3") (pinfunction "3_3") (pintype "passive"))
    )
    (net (code "130") (name "unconnected-(J4-Pad4)") (class "Default")
      (node (ref "J4") (pin "4") (pinfunction "4_4") (pintype "passive"))
    )
    (net (code "131") (name "unconnected-(J5-Pad3)") (class "Default")
      (node (ref "J5") (pin "3") (pinfunction "3_3") (pintype "passive"))
    )
    (net (code "132") (name "unconnected-(J5-Pad4)") (class "Default")
      (node (ref "J5") (pin "4") (pinfunction "4_4") (pintype "passive"))
    )
    (net (code "133") (name "unconnected-(J6-Pad3)") (class "Default")
      (node (ref "J6") (pin "3") (pinfunction "3_3") (pintype "passive"))
    )
    (net (code "134") (name "unconnected-(J6-Pad4)") (class "Default")
      (node (ref "J6") (pin "4") (pinfunction "4_4") (pintype "passive"))
    )
    (net (code "135") (name "unconnected-(J7-Pad3)") (class "Default")
      (node (ref "J7") (pin "3") (pinfunction "3_3") (pintype "passive"))
    )
    (net (code "136") (name "unconnected-(J7-Pad4)") (class "Default")
      (node (ref "J7") (pin "4") (pinfunction "4_4") (pintype "passive"))
    )
    (net (code "137") (name "unconnected-(J9-Pad6)") (class "Default")
      (node (ref "J9") (pin "6") (pinfunction "6_6") (pintype "passive"))
    )
    (net (code "138") (name "unconnected-(LCD1-DB0-Pad7)") (class "Default")
      (node (ref "LCD1") (pin "7") (pinfunction "DB0_7") (pintype "bidirectional"))
    )
    (net (code "139") (name "unconnected-(LCD1-DB1-Pad8)") (class "Default")
      (node (ref "LCD1") (pin "8") (pinfunction "DB1_8") (pintype "bidirectional"))
    )
    (net (code "140") (name "unconnected-(LCD1-DB2-Pad9)") (class "Default")
      (node (ref "LCD1") (pin "9") (pinfunction "DB2_9") (pintype "bidirectional"))
    )
    (net (code "141") (name "unconnected-(LCD1-DB3-Pad10)") (class "Default")
      (node (ref "LCD1") (pin "10") (pinfunction "DB3_10") (pintype "bidirectional"))
    )
    (net (code "142") (name "unconnected-(U1-(SS)PB4-Pad5)") (class "Default")
      (node (ref "U1") (pin "5") (pinfunction "(SS)PB4_5") (pintype "bidirectional"))
    )
    (net (code "143") (name "unconnected-(U4B-OUT-Pad7)") (class "Default")
      (node (ref "U4") (pin "7") (pinfunction "OUT_7") (pintype "output"))
    )
    (net (code "144") (name "~{CS}") (class "Default")
      (node (ref "U1") (pin "18") (pinfunction "(OC1B)PD4_18") (pintype "bidirectional"))
      (node (ref "U8A") (pin "3") (pinfunction "~{CS}_3") (pintype "bidirectional"))
      (node (ref "U8B") (pin "1") (pinfunction "1_1") (pintype "passive"))
    )
  )
)
